# Driver4BusV1_1.net
KiCad netlist of a schematic drawn in Altium Designer
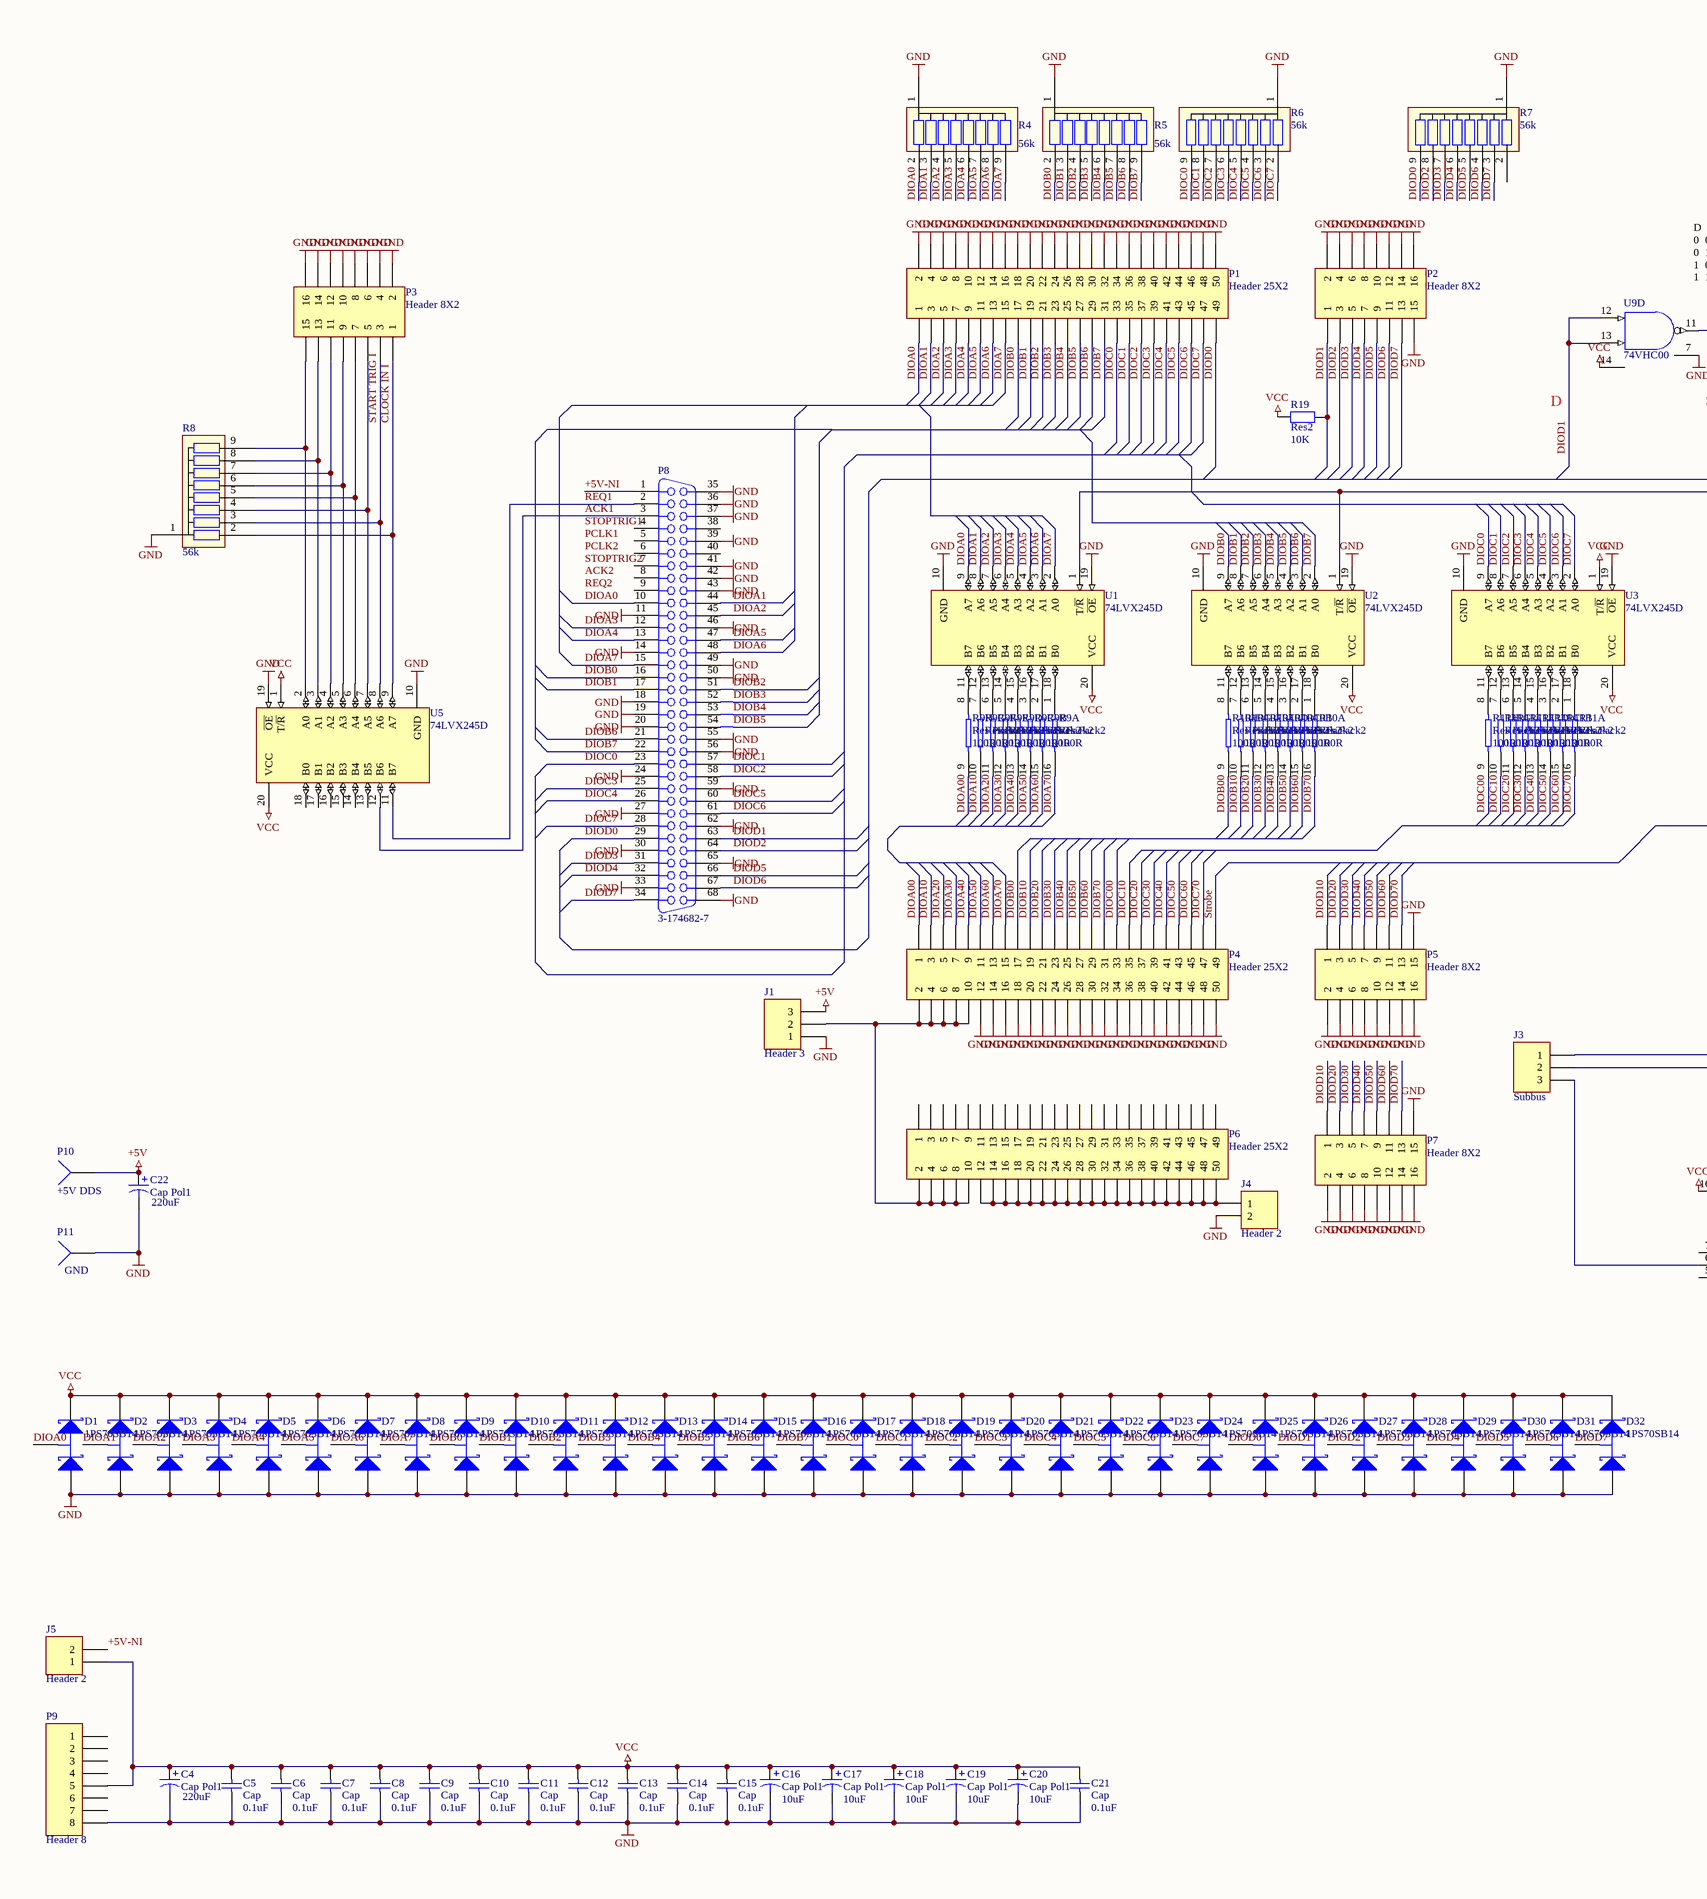
[diagram p0: Driver4BusV1.1.SchDoc, left]
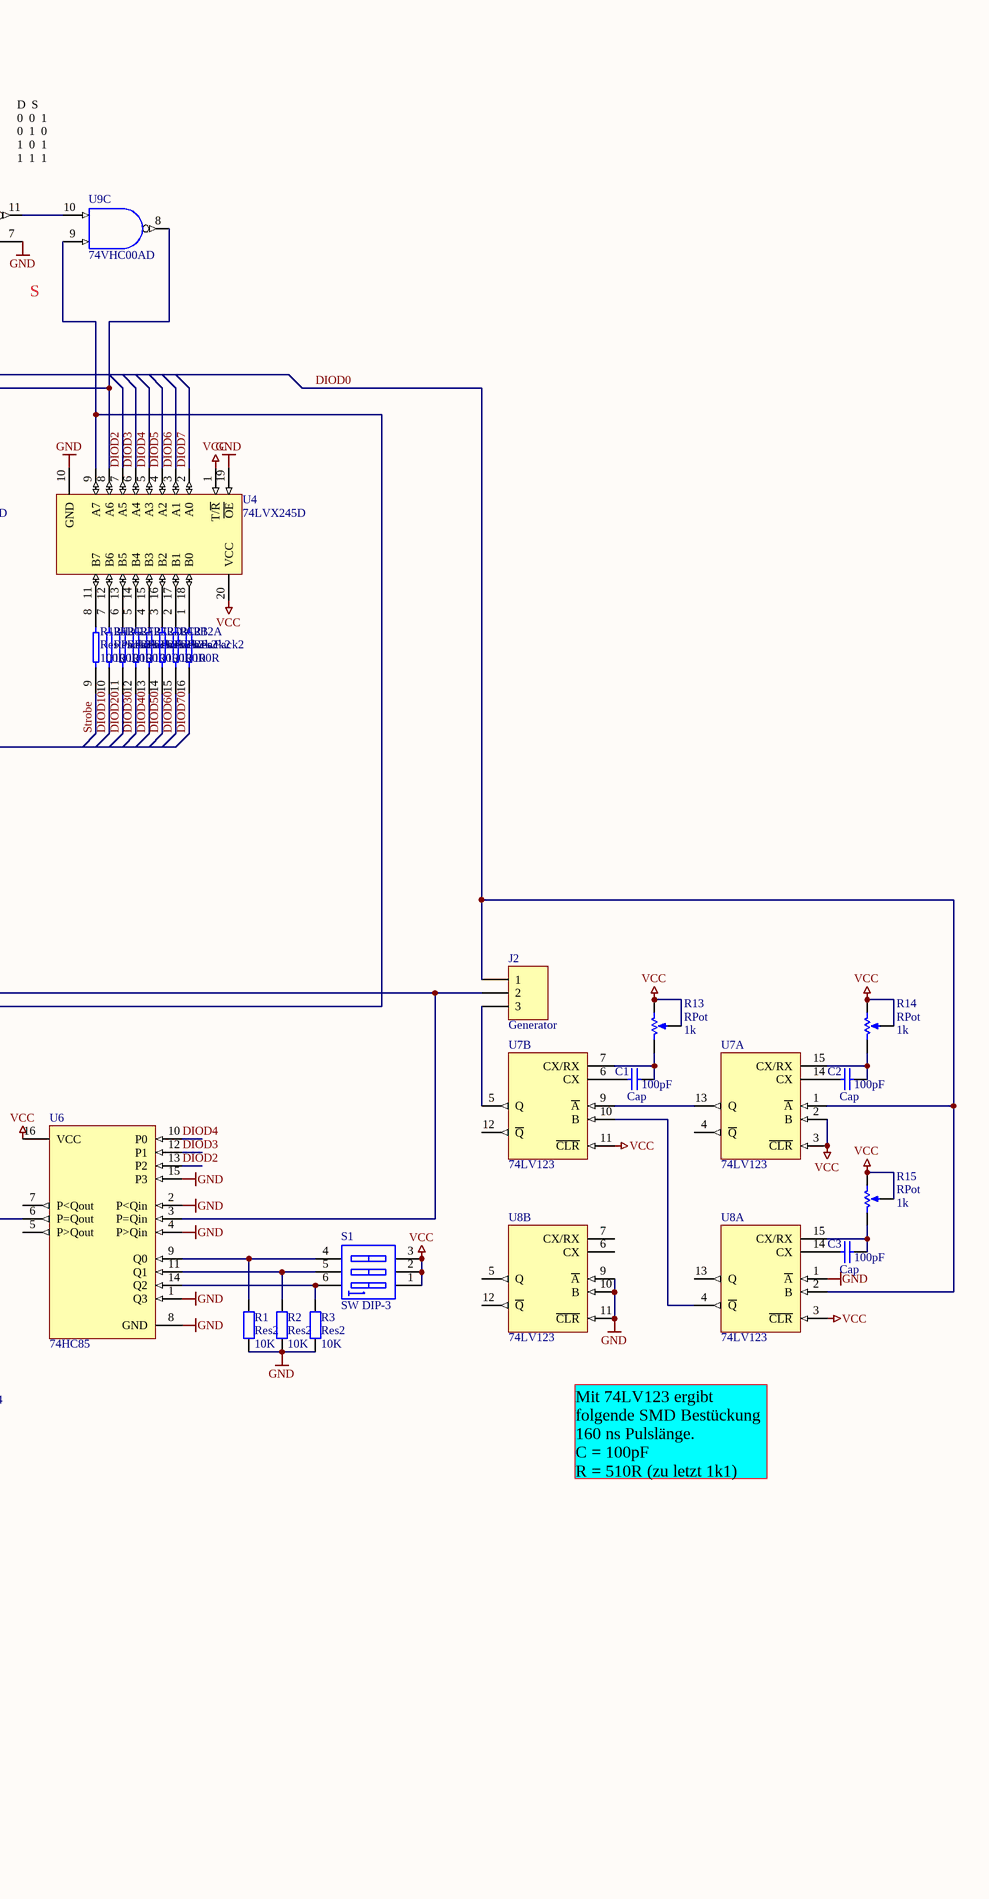
[diagram p1: Driver4BusV1.1.SchDoc, right]

(export (version "E")
  (design (tool "Eeschema 10.0.6"))
  (components
    (comp (ref "C1")
      (value "Cap")
      (footprint "CAPC3216M")
      (description "Capacitor")
      (fields (field (name "ALTIUM_VALUE") "100pF") (field (name "PUBLISHER") "Altium Limited"))
      (libsource (lib "Miscellaneous Devices") (part "Cap"))
    )
    (comp (ref "C2")
      (value "Cap")
      (footprint "CAPC3216M")
      (description "Capacitor")
      (fields (field (name "ALTIUM_VALUE") "100pF") (field (name "PUBLISHER") "Altium Limited"))
      (libsource (lib "Miscellaneous Devices") (part "Cap"))
    )
    (comp (ref "C3")
      (value "Cap")
      (footprint "CAPC3216M")
      (description "Capacitor")
      (fields (field (name "ALTIUM_VALUE") "100pF") (field (name "PUBLISHER") "Altium Limited"))
      (libsource (lib "Miscellaneous Devices") (part "Cap"))
    )
    (comp (ref "C4")
      (value "Cap Pol1")
      (footprint "ElkoSMD8")
      (description "Polarized Capacitor (Radial)")
      (fields (field (name "ALTIUM_VALUE") "220uF") (field (name "PUBLISHER") "Altium Limited"))
      (libsource (lib "Miscellaneous Devices") (part "Cap Pol1"))
    )
    (comp (ref "C5")
      (value "Cap")
      (footprint "CAPC3216M")
      (description "Capacitor")
      (fields (field (name "ALTIUM_VALUE") "0.1uF") (field (name "PUBLISHER") "Altium Limited"))
      (libsource (lib "Miscellaneous Devices") (part "Cap"))
    )
    (comp (ref "C6")
      (value "Cap")
      (footprint "CAPC3216M")
      (description "Capacitor")
      (fields (field (name "ALTIUM_VALUE") "0.1uF") (field (name "PUBLISHER") "Altium Limited"))
      (libsource (lib "Miscellaneous Devices") (part "Cap"))
    )
    (comp (ref "C7")
      (value "Cap")
      (footprint "CAPC3216M")
      (description "Capacitor")
      (fields (field (name "ALTIUM_VALUE") "0.1uF") (field (name "PUBLISHER") "Altium Limited"))
      (libsource (lib "Miscellaneous Devices") (part "Cap"))
    )
    (comp (ref "C8")
      (value "Cap")
      (footprint "CAPC3216M")
      (description "Capacitor")
      (fields (field (name "ALTIUM_VALUE") "0.1uF") (field (name "PUBLISHER") "Altium Limited"))
      (libsource (lib "Miscellaneous Devices") (part "Cap"))
    )
    (comp (ref "C9")
      (value "Cap")
      (footprint "CAPC3216M")
      (description "Capacitor")
      (fields (field (name "ALTIUM_VALUE") "0.1uF") (field (name "PUBLISHER") "Altium Limited"))
      (libsource (lib "Miscellaneous Devices") (part "Cap"))
    )
    (comp (ref "C10")
      (value "Cap")
      (footprint "CAPC3216M")
      (description "Capacitor")
      (fields (field (name "ALTIUM_VALUE") "0.1uF") (field (name "PUBLISHER") "Altium Limited"))
      (libsource (lib "Miscellaneous Devices") (part "Cap"))
    )
    (comp (ref "C11")
      (value "Cap")
      (footprint "CAPC3216M")
      (description "Capacitor")
      (fields (field (name "ALTIUM_VALUE") "0.1uF") (field (name "PUBLISHER") "Altium Limited"))
      (libsource (lib "Miscellaneous Devices") (part "Cap"))
    )
    (comp (ref "C12")
      (value "Cap")
      (footprint "CAPC3216M")
      (description "Capacitor")
      (fields (field (name "ALTIUM_VALUE") "0.1uF") (field (name "PUBLISHER") "Altium Limited"))
      (libsource (lib "Miscellaneous Devices") (part "Cap"))
    )
    (comp (ref "C13")
      (value "Cap")
      (footprint "CAPC3216M")
      (description "Capacitor")
      (fields (field (name "ALTIUM_VALUE") "0.1uF") (field (name "PUBLISHER") "Altium Limited"))
      (libsource (lib "Miscellaneous Devices") (part "Cap"))
    )
    (comp (ref "C14")
      (value "Cap")
      (footprint "CAPC3216M")
      (description "Capacitor")
      (fields (field (name "ALTIUM_VALUE") "0.1uF") (field (name "PUBLISHER") "Altium Limited"))
      (libsource (lib "Miscellaneous Devices") (part "Cap"))
    )
    (comp (ref "C15")
      (value "Cap")
      (footprint "CAPC3216M")
      (description "Capacitor")
      (fields (field (name "ALTIUM_VALUE") "0.1uF") (field (name "PUBLISHER") "Altium Limited"))
      (libsource (lib "Miscellaneous Devices") (part "Cap"))
    )
    (comp (ref "C16")
      (value "Cap Pol1")
      (footprint "TC3528-1411")
      (description "Polarized Capacitor (Radial)")
      (fields (field (name "ALTIUM_VALUE") "10uF") (field (name "PUBLISHER") "Altium Limited"))
      (libsource (lib "Miscellaneous Devices") (part "Cap Pol1"))
    )
    (comp (ref "C17")
      (value "Cap Pol1")
      (footprint "TC3528-1411")
      (description "Polarized Capacitor (Radial)")
      (fields (field (name "ALTIUM_VALUE") "10uF") (field (name "PUBLISHER") "Altium Limited"))
      (libsource (lib "Miscellaneous Devices") (part "Cap Pol1"))
    )
    (comp (ref "C18")
      (value "Cap Pol1")
      (footprint "TC3528-1411")
      (description "Polarized Capacitor (Radial)")
      (fields (field (name "ALTIUM_VALUE") "10uF") (field (name "PUBLISHER") "Altium Limited"))
      (libsource (lib "Miscellaneous Devices") (part "Cap Pol1"))
    )
    (comp (ref "C19")
      (value "Cap Pol1")
      (footprint "TC3528-1411")
      (description "Polarized Capacitor (Radial)")
      (fields (field (name "ALTIUM_VALUE") "10uF") (field (name "PUBLISHER") "Altium Limited"))
      (libsource (lib "Miscellaneous Devices") (part "Cap Pol1"))
    )
    (comp (ref "C20")
      (value "Cap Pol1")
      (footprint "TC3528-1411")
      (description "Polarized Capacitor (Radial)")
      (fields (field (name "ALTIUM_VALUE") "10uF") (field (name "PUBLISHER") "Altium Limited"))
      (libsource (lib "Miscellaneous Devices") (part "Cap Pol1"))
    )
    (comp (ref "C21")
      (value "Cap")
      (footprint "CAPC3216M")
      (description "Capacitor")
      (fields (field (name "ALTIUM_VALUE") "0.1uF") (field (name "PUBLISHER") "Altium Limited"))
      (libsource (lib "Miscellaneous Devices") (part "Cap"))
    )
    (comp (ref "C22")
      (value "Cap Pol1")
      (footprint "ElkoSMD8")
      (description "Polarized Capacitor (Radial)")
      (fields
        (field (name "ALTIUM_VALUE") "220uF")
        (field (name "VOLTAGE") "25V")
        (field (name "PUBLISHER") "Altium Limited")
      )
      (libsource (lib "Miscellaneous Devices") (part "Cap Pol1"))
    )
    (comp (ref "D1")
      (value "1PS70SB14")
      (footprint "SOT323")
      (description "Schottky Barrier Double Diode")
      (fields (field (name "PUBLISHER") "Altium Limited"))
      (libsource (lib "Philips Discrete Diode - Schottky") (part "1PS70SB14"))
    )
    (comp (ref "D2")
      (value "1PS70SB14")
      (footprint "SOT323")
      (description "Schottky Barrier Double Diode")
      (fields (field (name "PUBLISHER") "Altium Limited"))
      (libsource (lib "Philips Discrete Diode - Schottky") (part "1PS70SB14"))
    )
    (comp (ref "D3")
      (value "1PS70SB14")
      (footprint "SOT323")
      (description "Schottky Barrier Double Diode")
      (fields (field (name "PUBLISHER") "Altium Limited"))
      (libsource (lib "Philips Discrete Diode - Schottky") (part "1PS70SB14"))
    )
    (comp (ref "D4")
      (value "1PS70SB14")
      (footprint "SOT323")
      (description "Schottky Barrier Double Diode")
      (fields (field (name "PUBLISHER") "Altium Limited"))
      (libsource (lib "Philips Discrete Diode - Schottky") (part "1PS70SB14"))
    )
    (comp (ref "D5")
      (value "1PS70SB14")
      (footprint "SOT323")
      (description "Schottky Barrier Double Diode")
      (fields (field (name "PUBLISHER") "Altium Limited"))
      (libsource (lib "Philips Discrete Diode - Schottky") (part "1PS70SB14"))
    )
    (comp (ref "D6")
      (value "1PS70SB14")
      (footprint "SOT323")
      (description "Schottky Barrier Double Diode")
      (fields (field (name "PUBLISHER") "Altium Limited"))
      (libsource (lib "Philips Discrete Diode - Schottky") (part "1PS70SB14"))
    )
    (comp (ref "D7")
      (value "1PS70SB14")
      (footprint "SOT323")
      (description "Schottky Barrier Double Diode")
      (fields (field (name "PUBLISHER") "Altium Limited"))
      (libsource (lib "Philips Discrete Diode - Schottky") (part "1PS70SB14"))
    )
    (comp (ref "D8")
      (value "1PS70SB14")
      (footprint "SOT323")
      (description "Schottky Barrier Double Diode")
      (fields (field (name "PUBLISHER") "Altium Limited"))
      (libsource (lib "Philips Discrete Diode - Schottky") (part "1PS70SB14"))
    )
    (comp (ref "D9")
      (value "1PS70SB14")
      (footprint "SOT323")
      (description "Schottky Barrier Double Diode")
      (fields (field (name "PUBLISHER") "Altium Limited"))
      (libsource (lib "Philips Discrete Diode - Schottky") (part "1PS70SB14"))
    )
    (comp (ref "D10")
      (value "1PS70SB14")
      (footprint "SOT323")
      (description "Schottky Barrier Double Diode")
      (fields (field (name "PUBLISHER") "Altium Limited"))
      (libsource (lib "Philips Discrete Diode - Schottky") (part "1PS70SB14"))
    )
    (comp (ref "D11")
      (value "1PS70SB14")
      (footprint "SOT323")
      (description "Schottky Barrier Double Diode")
      (fields (field (name "PUBLISHER") "Altium Limited"))
      (libsource (lib "Philips Discrete Diode - Schottky") (part "1PS70SB14"))
    )
    (comp (ref "D12")
      (value "1PS70SB14")
      (footprint "SOT323")
      (description "Schottky Barrier Double Diode")
      (fields (field (name "PUBLISHER") "Altium Limited"))
      (libsource (lib "Philips Discrete Diode - Schottky") (part "1PS70SB14"))
    )
    (comp (ref "D13")
      (value "1PS70SB14")
      (footprint "SOT323")
      (description "Schottky Barrier Double Diode")
      (fields (field (name "PUBLISHER") "Altium Limited"))
      (libsource (lib "Philips Discrete Diode - Schottky") (part "1PS70SB14"))
    )
    (comp (ref "D14")
      (value "1PS70SB14")
      (footprint "SOT323")
      (description "Schottky Barrier Double Diode")
      (fields (field (name "PUBLISHER") "Altium Limited"))
      (libsource (lib "Philips Discrete Diode - Schottky") (part "1PS70SB14"))
    )
    (comp (ref "D15")
      (value "1PS70SB14")
      (footprint "SOT323")
      (description "Schottky Barrier Double Diode")
      (fields (field (name "PUBLISHER") "Altium Limited"))
      (libsource (lib "Philips Discrete Diode - Schottky") (part "1PS70SB14"))
    )
    (comp (ref "D16")
      (value "1PS70SB14")
      (footprint "SOT323")
      (description "Schottky Barrier Double Diode")
      (fields (field (name "PUBLISHER") "Altium Limited"))
      (libsource (lib "Philips Discrete Diode - Schottky") (part "1PS70SB14"))
    )
    (comp (ref "D17")
      (value "1PS70SB14")
      (footprint "SOT323")
      (description "Schottky Barrier Double Diode")
      (fields (field (name "PUBLISHER") "Altium Limited"))
      (libsource (lib "Philips Discrete Diode - Schottky") (part "1PS70SB14"))
    )
    (comp (ref "D18")
      (value "1PS70SB14")
      (footprint "SOT323")
      (description "Schottky Barrier Double Diode")
      (fields (field (name "PUBLISHER") "Altium Limited"))
      (libsource (lib "Philips Discrete Diode - Schottky") (part "1PS70SB14"))
    )
    (comp (ref "D19")
      (value "1PS70SB14")
      (footprint "SOT323")
      (description "Schottky Barrier Double Diode")
      (fields (field (name "PUBLISHER") "Altium Limited"))
      (libsource (lib "Philips Discrete Diode - Schottky") (part "1PS70SB14"))
    )
    (comp (ref "D20")
      (value "1PS70SB14")
      (footprint "SOT323")
      (description "Schottky Barrier Double Diode")
      (fields (field (name "PUBLISHER") "Altium Limited"))
      (libsource (lib "Philips Discrete Diode - Schottky") (part "1PS70SB14"))
    )
    (comp (ref "D21")
      (value "1PS70SB14")
      (footprint "SOT323")
      (description "Schottky Barrier Double Diode")
      (fields (field (name "PUBLISHER") "Altium Limited"))
      (libsource (lib "Philips Discrete Diode - Schottky") (part "1PS70SB14"))
    )
    (comp (ref "D22")
      (value "1PS70SB14")
      (footprint "SOT323")
      (description "Schottky Barrier Double Diode")
      (fields (field (name "PUBLISHER") "Altium Limited"))
      (libsource (lib "Philips Discrete Diode - Schottky") (part "1PS70SB14"))
    )
    (comp (ref "D23")
      (value "1PS70SB14")
      (footprint "SOT323")
      (description "Schottky Barrier Double Diode")
      (fields (field (name "PUBLISHER") "Altium Limited"))
      (libsource (lib "Philips Discrete Diode - Schottky") (part "1PS70SB14"))
    )
    (comp (ref "D24")
      (value "1PS70SB14")
      (footprint "SOT323")
      (description "Schottky Barrier Double Diode")
      (fields (field (name "PUBLISHER") "Altium Limited"))
      (libsource (lib "Philips Discrete Diode - Schottky") (part "1PS70SB14"))
    )
    (comp (ref "D25")
      (value "1PS70SB14")
      (footprint "SOT323")
      (description "Schottky Barrier Double Diode")
      (fields (field (name "PUBLISHER") "Altium Limited"))
      (libsource (lib "Philips Discrete Diode - Schottky") (part "1PS70SB14"))
    )
    (comp (ref "D26")
      (value "1PS70SB14")
      (footprint "SOT323")
      (description "Schottky Barrier Double Diode")
      (fields (field (name "PUBLISHER") "Altium Limited"))
      (libsource (lib "Philips Discrete Diode - Schottky") (part "1PS70SB14"))
    )
    (comp (ref "D27")
      (value "1PS70SB14")
      (footprint "SOT323")
      (description "Schottky Barrier Double Diode")
      (fields (field (name "PUBLISHER") "Altium Limited"))
      (libsource (lib "Philips Discrete Diode - Schottky") (part "1PS70SB14"))
    )
    (comp (ref "D28")
      (value "1PS70SB14")
      (footprint "SOT323")
      (description "Schottky Barrier Double Diode")
      (fields (field (name "PUBLISHER") "Altium Limited"))
      (libsource (lib "Philips Discrete Diode - Schottky") (part "1PS70SB14"))
    )
    (comp (ref "D29")
      (value "1PS70SB14")
      (footprint "SOT323")
      (description "Schottky Barrier Double Diode")
      (fields (field (name "PUBLISHER") "Altium Limited"))
      (libsource (lib "Philips Discrete Diode - Schottky") (part "1PS70SB14"))
    )
    (comp (ref "D30")
      (value "1PS70SB14")
      (footprint "SOT323")
      (description "Schottky Barrier Double Diode")
      (fields (field (name "PUBLISHER") "Altium Limited"))
      (libsource (lib "Philips Discrete Diode - Schottky") (part "1PS70SB14"))
    )
    (comp (ref "D31")
      (value "1PS70SB14")
      (footprint "SOT323")
      (description "Schottky Barrier Double Diode")
      (fields (field (name "PUBLISHER") "Altium Limited"))
      (libsource (lib "Philips Discrete Diode - Schottky") (part "1PS70SB14"))
    )
    (comp (ref "D32")
      (value "1PS70SB14")
      (footprint "SOT323")
      (description "Schottky Barrier Double Diode")
      (fields (field (name "PUBLISHER") "Altium Limited"))
      (libsource (lib "Philips Discrete Diode - Schottky") (part "1PS70SB14"))
    )
    (comp (ref "J1")
      (value "Header 3")
      (footprint "HDR1X3")
      (description "Header, 3-Pin")
      (fields (field (name "PUBLISHER") "Altium Limited"))
      (libsource (lib "") (part "Header 3_2"))
    )
    (comp (ref "J2")
      (value "Generator")
      (footprint "HDR1X3")
      (description "Header, 3-Pin")
      (fields (field (name "PUBLISHER") "Altium Limited"))
      (libsource (lib "") (part "Header 3_1"))
    )
    (comp (ref "J3")
      (value "Subbus")
      (footprint "HDR1X3")
      (description "Header, 3-Pin")
      (fields (field (name "PUBLISHER") "Altium Limited"))
      (libsource (lib "Miscellaneous Connectors") (part "Header 3"))
    )
    (comp (ref "J4")
      (value "Header 2")
      (footprint "RESC2012M")
      (description "Header, 2-Pin")
      (fields (field (name "PUBLISHER") "Altium Limited"))
      (libsource (lib "Miscellaneous Connectors") (part "Header 2"))
    )
    (comp (ref "J5")
      (value "Header 2")
      (footprint "RESC2012M")
      (description "Header, 2-Pin")
      (fields (field (name "PUBLISHER") "Altium Limited"))
      (libsource (lib "") (part "Header 2_1"))
    )
    (comp (ref "P1")
      (value "Header 25X2")
      (footprint "HDR2X25")
      (description "Header, 25-Pin, Dual row")
      (fields (field (name "PUBLISHER") "Altium Limited"))
      (libsource (lib "") (part "Header 25X2_1"))
    )
    (comp (ref "P2")
      (value "Header 8X2")
      (footprint "HDR2X8")
      (description "Header, 8-Pin, Dual row")
      (fields (field (name "PUBLISHER") "Altium Limited"))
      (libsource (lib "") (part "Header 8X2_2"))
    )
    (comp (ref "P3")
      (value "Header 8X2")
      (footprint "HDR2X8")
      (description "Header, 8-Pin, Dual row")
      (fields (field (name "PUBLISHER") "Altium Limited"))
      (libsource (lib "Miscellaneous Connectors") (part "Header 8X2"))
    )
    (comp (ref "P4")
      (value "Header 25X2")
      (footprint "HDR2X25")
      (description "Header, 25-Pin, Dual row")
      (fields (field (name "PUBLISHER") "Altium Limited"))
      (libsource (lib "Miscellaneous Connectors") (part "Header 25X2"))
    )
    (comp (ref "P5")
      (value "Header 8X2")
      (footprint "HDR2X8")
      (description "Header, 8-Pin, Dual row")
      (fields (field (name "PUBLISHER") "Altium Limited"))
      (libsource (lib "") (part "Header 8X2_1"))
    )
    (comp (ref "P6")
      (value "Header 25X2")
      (footprint "HDR2X25")
      (description "Header, 25-Pin, Dual row")
      (fields (field (name "PUBLISHER") "Altium Limited"))
      (libsource (lib "Miscellaneous Connectors") (part "Header 25X2"))
    )
    (comp (ref "P7")
      (value "Header 8X2")
      (footprint "HDR2X8")
      (description "Header, 8-Pin, Dual row")
      (fields (field (name "PUBLISHER") "Altium Limited"))
      (libsource (lib "") (part "Header 8X2_1"))
    )
    (comp (ref "P8")
      (value "3-174682-7")
      (footprint "174225-5")
      (description "Plug Assembly, Horizontal with Kink")
      (fields (field (name "PUBLISHER") "Altium Limited"))
      (libsource (lib "AMP D Subminiature 050 Series") (part "3-174682-7"))
    )
    (comp (ref "P9")
      (value "Header 8")
      (footprint "DIN 8-polig V2")
      (description "Header, 8-Pin")
      (fields (field (name "PUBLISHER") "Altium Limited"))
      (libsource (lib "Miscellaneous Connectors") (part "Header 8"))
    )
    (comp (ref "P10")
      (value "+5V DDS")
      (footprint "Banane on BCP")
      (description "Socket")
      (fields (field (name "PUBLISHER") "Altium Limited"))
      (libsource (lib "Miscellaneous Connectors") (part "Socket"))
    )
    (comp (ref "P11")
      (value "GND")
      (footprint "Banane on BCP")
      (description "Socket")
      (fields (field (name "PUBLISHER") "Altium Limited"))
      (libsource (lib "Miscellaneous Connectors") (part "Socket"))
    )
    (comp (ref "R1")
      (value "Res2")
      (footprint "3216[1206]")
      (description "Resistor")
      (fields (field (name "ALTIUM_VALUE") "10K") (field (name "PUBLISHER") "Altium Limited"))
      (libsource (lib "Miscellaneous Devices") (part "Res2"))
    )
    (comp (ref "R2")
      (value "Res2")
      (footprint "3216[1206]")
      (description "Resistor")
      (fields (field (name "ALTIUM_VALUE") "10K") (field (name "PUBLISHER") "Altium Limited"))
      (libsource (lib "Miscellaneous Devices") (part "Res2"))
    )
    (comp (ref "R3")
      (value "Res2")
      (footprint "3216[1206]")
      (description "Resistor")
      (fields (field (name "ALTIUM_VALUE") "10K") (field (name "PUBLISHER") "Altium Limited"))
      (libsource (lib "Miscellaneous Devices") (part "Res2"))
    )
    (comp (ref "R4")
      (value "56k")
      (footprint "Widerstandnetzwerk 4609X")
      (fields (field (name "Comment") "Widerstandnetzwerk 4609X"))
      (libsource (lib "") (part "Widerstandnetzwerk 4609X_1"))
    )
    (comp (ref "R5")
      (value "56k")
      (footprint "Widerstandnetzwerk 4609X")
      (fields (field (name "Comment") "Widerstandnetzwerk 4609X"))
      (libsource (lib "") (part "Widerstandnetzwerk 4609X_1"))
    )
    (comp (ref "R6")
      (value "56k")
      (footprint "Widerstandnetzwerk 4609X")
      (fields (field (name "Comment") "Widerstandnetzwerk 4609X"))
      (libsource (lib "eigene") (part "Widerstandnetzwerk 4609X"))
    )
    (comp (ref "R7")
      (value "56k")
      (footprint "Widerstandnetzwerk 4609X")
      (fields (field (name "Comment") "Widerstandnetzwerk 4609X"))
      (libsource (lib "eigene") (part "Widerstandnetzwerk 4609X"))
    )
    (comp (ref "R8")
      (value "56k")
      (footprint "Widerstandnetzwerk 4609X")
      (fields (field (name "Comment") "Widerstandnetzwerk 4609X"))
      (libsource (lib "") (part "Widerstandnetzwerk 4609X_2"))
    )
    (comp (ref "R9")
      (value "Res Pack2")
      (footprint "SOIC-OE16_M")
      (description "Isolated Resistor Network - Parts")
      (fields (field (name "ALTIUM_VALUE") "100R") (field (name "PUBLISHER") "Altium Limited"))
      (libsource (lib "Miscellaneous Devices") (part "Res Pack2"))
    )
    (comp (ref "R10")
      (value "Res Pack2")
      (footprint "SOIC-OE16_M")
      (description "Isolated Resistor Network - Parts")
      (fields (field (name "ALTIUM_VALUE") "100R") (field (name "PUBLISHER") "Altium Limited"))
      (libsource (lib "Miscellaneous Devices") (part "Res Pack2"))
    )
    (comp (ref "R11")
      (value "Res Pack2")
      (footprint "SOIC-OE16_M")
      (description "Isolated Resistor Network - Parts")
      (fields (field (name "ALTIUM_VALUE") "100R") (field (name "PUBLISHER") "Altium Limited"))
      (libsource (lib "Miscellaneous Devices") (part "Res Pack2"))
    )
    (comp (ref "R12")
      (value "Res Pack2")
      (footprint "SOIC-OE16_M")
      (description "Isolated Resistor Network - Parts")
      (fields (field (name "ALTIUM_VALUE") "100R") (field (name "PUBLISHER") "Altium Limited"))
      (libsource (lib "Miscellaneous Devices") (part "Res Pack2"))
    )
    (comp (ref "R13")
      (value "RPot")
      (footprint "rpot3")
      (description "Potentiometer")
      (fields (field (name "ALTIUM_VALUE") "1k") (field (name "PUBLISHER") "Altium Limited"))
      (libsource (lib "Miscellaneous Devices") (part "RPot"))
    )
    (comp (ref "R14")
      (value "RPot")
      (footprint "rpot3")
      (description "Potentiometer")
      (fields (field (name "ALTIUM_VALUE") "1k") (field (name "PUBLISHER") "Altium Limited"))
      (libsource (lib "Miscellaneous Devices") (part "RPot"))
    )
    (comp (ref "R15")
      (value "RPot")
      (footprint "rpot3")
      (description "Potentiometer")
      (fields (field (name "ALTIUM_VALUE") "1k") (field (name "PUBLISHER") "Altium Limited"))
      (libsource (lib "Miscellaneous Devices") (part "RPot"))
    )
    (comp (ref "R19")
      (value "Res2")
      (footprint "3216[1206]")
      (description "Resistor")
      (fields (field (name "ALTIUM_VALUE") "10K") (field (name "PUBLISHER") "Altium Limited"))
      (libsource (lib "") (part "Res2_1"))
    )
    (comp (ref "S1")
      (value "SW DIP-3")
      (footprint "DIP-6")
      (description "DIP Switch, 3 Position, SPST")
      (fields (field (name "PUBLISHER") "Altium Limited"))
      (libsource (lib "Miscellaneous Devices") (part "SW DIP-3"))
    )
    (comp (ref "U1")
      (value "74LVX245D")
      (footprint "DW020_N")
      (description "Octal Bus Transceiver with 3-State Outputs")
      (fields (field (name "PUBLISHER") "Altium Limited"))
      (libsource (lib "TI Interface 8-Bit Line Transceiver") (part "SN74HC245DW"))
    )
    (comp (ref "U2")
      (value "74LVX245D")
      (footprint "DW020_N")
      (description "Octal Bus Transceiver with 3-State Outputs")
      (fields (field (name "PUBLISHER") "Altium Limited"))
      (libsource (lib "TI Interface 8-Bit Line Transceiver") (part "SN74HC245DW"))
    )
    (comp (ref "U3")
      (value "74LVX245D")
      (footprint "DW020_N")
      (description "Octal Bus Transceiver with 3-State Outputs")
      (fields (field (name "PUBLISHER") "Altium Limited"))
      (libsource (lib "TI Interface 8-Bit Line Transceiver") (part "SN74HC245DW"))
    )
    (comp (ref "U4")
      (value "74LVX245D")
      (footprint "DW020_N")
      (description "Octal Bus Transceiver with 3-State Outputs")
      (fields (field (name "PUBLISHER") "Altium Limited"))
      (libsource (lib "TI Interface 8-Bit Line Transceiver") (part "SN74HC245DW"))
    )
    (comp (ref "U5")
      (value "74LVX245D")
      (footprint "DW020_N")
      (description "Octal Bus Transceiver with 3-State Outputs")
      (fields (field (name "PUBLISHER") "Altium Limited"))
      (libsource (lib "") (part "SN74HC245DW_1"))
    )
    (comp (ref "U6")
      (value "74HC85")
      (footprint "SO16_M")
      (description "4-Bit Magnitude Comparator")
      (fields (field (name "PUBLISHER") "Altium Limited"))
      (libsource (lib "ST Logic Comparator") (part "M74HC85M1R"))
    )
    (comp (ref "U7")
      (value "74LV123")
      (footprint "SO16_N")
      (description "Dual Retriggerable Monostable Multivibrator")
      (fields (field (name "PUBLISHER") "Altium Limited"))
      (libsource (lib "ST Logic Multivibrator") (part "M74HC123AM1R"))
    )
    (comp (ref "U8")
      (value "74LV123")
      (footprint "SO16_N")
      (description "Dual Retriggerable Monostable Multivibrator")
      (fields (field (name "PUBLISHER") "Altium Limited"))
      (libsource (lib "ST Logic Multivibrator") (part "M74HC123AM1R"))
    )
    (comp (ref "U9")
      (value "74VHC00AD")
      (footprint "751A-02_N")
      (description "Quad 2-Input NAND Gate")
      (fields (field (name "PUBLISHER") "Altium Limited"))
      (libsource (lib "") (part "MC74HC00AD_1"))
    )
  )
  (nets
    (net (code "1") (name "+5V") (class "Default")
      (node (ref "C22") (pin "1") (pinfunction "1_1") (pintype "passive"))
      (node (ref "J1") (pin "3") (pinfunction "3_3") (pintype "passive"))
      (node (ref "P10") (pin "1") (pinfunction "1_1") (pintype "passive"))
    )
    (net (code "2") (name "/+5V-NI") (class "Default")
      (node (ref "J5") (pin "2") (pinfunction "2_2") (pintype "passive"))
      (node (ref "P8") (pin "1") (pinfunction "1_1") (pintype "passive"))
    )
    (net (code "3") (name "/ACK1") (class "Default")
      (node (ref "P8") (pin "3") (pinfunction "3_3") (pintype "passive"))
      (node (ref "U5") (pin "12") (pinfunction "B6_12") (pintype "bidirectional"))
    )
    (net (code "5") (name "/CLOCK IN I") (class "Default")
      (node (ref "P3") (pin "1") (pinfunction "1_1") (pintype "passive"))
      (node (ref "R8") (pin "2") (pinfunction "2_2") (pintype "passive"))
      (node (ref "U5") (pin "9") (pinfunction "A7_9") (pintype "bidirectional"))
    )
    (net (code "6") (name "/DIOA00") (class "Default")
      (node (ref "P4") (pin "1") (pinfunction "1_1") (pintype "passive"))
      (node (ref "R9") (pin "9") (pinfunction "9_9") (pintype "passive"))
    )
    (net (code "7") (name "/DIOA0") (class "Default")
      (node (ref "D1") (pin "3") (pinfunction "C_3") (pintype "passive"))
      (node (ref "P1") (pin "1") (pinfunction "1_1") (pintype "passive"))
      (node (ref "P8") (pin "10") (pinfunction "10_10") (pintype "passive"))
      (node (ref "R4") (pin "2") (pinfunction "2_2") (pintype "passive"))
      (node (ref "U1") (pin "9") (pinfunction "A7_9") (pintype "bidirectional"))
    )
    (net (code "8") (name "/DIOA1") (class "Default")
      (node (ref "D2") (pin "3") (pinfunction "C_3") (pintype "passive"))
      (node (ref "P1") (pin "3") (pinfunction "3_3") (pintype "passive"))
      (node (ref "P8") (pin "44") (pinfunction "44_44") (pintype "passive"))
      (node (ref "R4") (pin "3") (pinfunction "3_3") (pintype "passive"))
      (node (ref "U1") (pin "8") (pinfunction "A6_8") (pintype "bidirectional"))
    )
    (net (code "9") (name "/DIOA2") (class "Default")
      (node (ref "D3") (pin "3") (pinfunction "C_3") (pintype "passive"))
      (node (ref "P1") (pin "5") (pinfunction "5_5") (pintype "passive"))
      (node (ref "P8") (pin "45") (pinfunction "45_45") (pintype "passive"))
      (node (ref "R4") (pin "4") (pinfunction "4_4") (pintype "passive"))
      (node (ref "U1") (pin "7") (pinfunction "A5_7") (pintype "bidirectional"))
    )
    (net (code "10") (name "/DIOA3") (class "Default")
      (node (ref "D4") (pin "3") (pinfunction "C_3") (pintype "passive"))
      (node (ref "P1") (pin "7") (pinfunction "7_7") (pintype "passive"))
      (node (ref "P8") (pin "12") (pinfunction "12_12") (pintype "passive"))
      (node (ref "R4") (pin "5") (pinfunction "5_5") (pintype "passive"))
      (node (ref "U1") (pin "6") (pinfunction "A4_6") (pintype "bidirectional"))
    )
    (net (code "11") (name "/DIOA4") (class "Default")
      (node (ref "D5") (pin "3") (pinfunction "C_3") (pintype "passive"))
      (node (ref "P1") (pin "9") (pinfunction "9_9") (pintype "passive"))
      (node (ref "P8") (pin "13") (pinfunction "13_13") (pintype "passive"))
      (node (ref "R4") (pin "6") (pinfunction "6_6") (pintype "passive"))
      (node (ref "U1") (pin "5") (pinfunction "A3_5") (pintype "bidirectional"))
    )
    (net (code "12") (name "/DIOA5") (class "Default")
      (node (ref "D6") (pin "3") (pinfunction "C_3") (pintype "passive"))
      (node (ref "P1") (pin "11") (pinfunction "11_11") (pintype "passive"))
      (node (ref "P8") (pin "47") (pinfunction "47_47") (pintype "passive"))
      (node (ref "R4") (pin "7") (pinfunction "7_7") (pintype "passive"))
      (node (ref "U1") (pin "4") (pinfunction "A2_4") (pintype "bidirectional"))
    )
    (net (code "13") (name "/DIOA6") (class "Default")
      (node (ref "D7") (pin "3") (pinfunction "C_3") (pintype "passive"))
      (node (ref "P1") (pin "13") (pinfunction "13_13") (pintype "passive"))
      (node (ref "P8") (pin "48") (pinfunction "48_48") (pintype "passive"))
      (node (ref "R4") (pin "8") (pinfunction "8_8") (pintype "passive"))
      (node (ref "U1") (pin "3") (pinfunction "A1_3") (pintype "bidirectional"))
    )
    (net (code "14") (name "/DIOA7") (class "Default")
      (node (ref "D8") (pin "3") (pinfunction "C_3") (pintype "passive"))
      (node (ref "P1") (pin "15") (pinfunction "15_15") (pintype "passive"))
      (node (ref "P8") (pin "15") (pinfunction "15_15") (pintype "passive"))
      (node (ref "R4") (pin "9") (pinfunction "9_9") (pintype "passive"))
      (node (ref "U1") (pin "2") (pinfunction "A0_2") (pintype "bidirectional"))
    )
    (net (code "15") (name "/DIOA10") (class "Default")
      (node (ref "P4") (pin "3") (pinfunction "3_3") (pintype "passive"))
      (node (ref "R9") (pin "10") (pinfunction "10_10") (pintype "passive"))
    )
    (net (code "16") (name "/DIOA20") (class "Default")
      (node (ref "P4") (pin "5") (pinfunction "5_5") (pintype "passive"))
      (node (ref "R9") (pin "11") (pinfunction "11_11") (pintype "passive"))
    )
    (net (code "17") (name "/DIOA30") (class "Default")
      (node (ref "P4") (pin "7") (pinfunction "7_7") (pintype "passive"))
      (node (ref "R9") (pin "12") (pinfunction "12_12") (pintype "passive"))
    )
    (net (code "18") (name "/DIOA40") (class "Default")
      (node (ref "P4") (pin "9") (pinfunction "9_9") (pintype "passive"))
      (node (ref "R9") (pin "13") (pinfunction "13_13") (pintype "passive"))
    )
    (net (code "19") (name "/DIOA50") (class "Default")
      (node (ref "P4") (pin "11") (pinfunction "11_11") (pintype "passive"))
      (node (ref "R9") (pin "14") (pinfunction "14_14") (pintype "passive"))
    )
    (net (code "20") (name "/DIOA60") (class "Default")
      (node (ref "P4") (pin "13") (pinfunction "13_13") (pintype "passive"))
      (node (ref "R9") (pin "15") (pinfunction "15_15") (pintype "passive"))
    )
    (net (code "21") (name "/DIOA70") (class "Default")
      (node (ref "P4") (pin "15") (pinfunction "15_15") (pintype "passive"))
      (node (ref "R9") (pin "16") (pinfunction "16_16") (pintype "passive"))
    )
    (net (code "22") (name "/DIOB0") (class "Default")
      (node (ref "D9") (pin "3") (pinfunction "C_3") (pintype "passive"))
      (node (ref "P1") (pin "17") (pinfunction "17_17") (pintype "passive"))
      (node (ref "P8") (pin "16") (pinfunction "16_16") (pintype "passive"))
      (node (ref "R5") (pin "2") (pinfunction "2_2") (pintype "passive"))
      (node (ref "U2") (pin "9") (pinfunction "A7_9") (pintype "bidirectional"))
    )
    (net (code "23") (name "/DIOB00") (class "Default")
      (node (ref "P4") (pin "17") (pinfunction "17_17") (pintype "passive"))
      (node (ref "R10") (pin "9") (pinfunction "9_9") (pintype "passive"))
    )
    (net (code "24") (name "/DIOB1") (class "Default")
      (node (ref "D10") (pin "3") (pinfunction "C_3") (pintype "passive"))
      (node (ref "P1") (pin "19") (pinfunction "19_19") (pintype "passive"))
      (node (ref "P8") (pin "17") (pinfunction "17_17") (pintype "passive"))
      (node (ref "R5") (pin "3") (pinfunction "3_3") (pintype "passive"))
      (node (ref "U2") (pin "8") (pinfunction "A6_8") (pintype "bidirectional"))
    )
    (net (code "25") (name "/DIOB2") (class "Default")
      (node (ref "D11") (pin "3") (pinfunction "C_3") (pintype "passive"))
      (node (ref "P1") (pin "21") (pinfunction "21_21") (pintype "passive"))
      (node (ref "P8") (pin "51") (pinfunction "51_51") (pintype "passive"))
      (node (ref "R5") (pin "4") (pinfunction "4_4") (pintype "passive"))
      (node (ref "U2") (pin "7") (pinfunction "A5_7") (pintype "bidirectional"))
    )
    (net (code "26") (name "/DIOB3") (class "Default")
      (node (ref "D12") (pin "3") (pinfunction "C_3") (pintype "passive"))
      (node (ref "P1") (pin "23") (pinfunction "23_23") (pintype "passive"))
      (node (ref "P8") (pin "52") (pinfunction "52_52") (pintype "passive"))
      (node (ref "R5") (pin "5") (pinfunction "5_5") (pintype "passive"))
      (node (ref "U2") (pin "6") (pinfunction "A4_6") (pintype "bidirectional"))
    )
    (net (code "27") (name "/DIOB4") (class "Default")
      (node (ref "D13") (pin "3") (pinfunction "C_3") (pintype "passive"))
      (node (ref "P1") (pin "25") (pinfunction "25_25") (pintype "passive"))
      (node (ref "P8") (pin "53") (pinfunction "53_53") (pintype "passive"))
      (node (ref "R5") (pin "6") (pinfunction "6_6") (pintype "passive"))
      (node (ref "U2") (pin "5") (pinfunction "A3_5") (pintype "bidirectional"))
    )
    (net (code "28") (name "/DIOB5") (class "Default")
      (node (ref "D14") (pin "3") (pinfunction "C_3") (pintype "passive"))
      (node (ref "P1") (pin "27") (pinfunction "27_27") (pintype "passive"))
      (node (ref "P8") (pin "54") (pinfunction "54_54") (pintype "passive"))
      (node (ref "R5") (pin "7") (pinfunction "7_7") (pintype "passive"))
      (node (ref "U2") (pin "4") (pinfunction "A2_4") (pintype "bidirectional"))
    )
    (net (code "29") (name "/DIOB6") (class "Default")
      (node (ref "D15") (pin "3") (pinfunction "C_3") (pintype "passive"))
      (node (ref "P1") (pin "29") (pinfunction "29_29") (pintype "passive"))
      (node (ref "P8") (pin "21") (pinfunction "21_21") (pintype "passive"))
      (node (ref "R5") (pin "8") (pinfunction "8_8") (pintype "passive"))
      (node (ref "U2") (pin "3") (pinfunction "A1_3") (pintype "bidirectional"))
    )
    (net (code "30") (name "/DIOB7") (class "Default")
      (node (ref "D16") (pin "3") (pinfunction "C_3") (pintype "passive"))
      (node (ref "P1") (pin "31") (pinfunction "31_31") (pintype "passive"))
      (node (ref "P8") (pin "22") (pinfunction "22_22") (pintype "passive"))
      (node (ref "R5") (pin "9") (pinfunction "9_9") (pintype "passive"))
      (node (ref "U2") (pin "2") (pinfunction "A0_2") (pintype "bidirectional"))
    )
    (net (code "31") (name "/DIOB10") (class "Default")
      (node (ref "P4") (pin "19") (pinfunction "19_19") (pintype "passive"))
      (node (ref "R10") (pin "10") (pinfunction "10_10") (pintype "passive"))
    )
    (net (code "32") (name "/DIOB20") (class "Default")
      (node (ref "P4") (pin "21") (pinfunction "21_21") (pintype "passive"))
      (node (ref "R10") (pin "11") (pinfunction "11_11") (pintype "passive"))
    )
    (net (code "33") (name "/DIOB30") (class "Default")
      (node (ref "P4") (pin "23") (pinfunction "23_23") (pintype "passive"))
      (node (ref "R10") (pin "12") (pinfunction "12_12") (pintype "passive"))
    )
    (net (code "34") (name "/DIOB40") (class "Default")
      (node (ref "P4") (pin "25") (pinfunction "25_25") (pintype "passive"))
      (node (ref "R10") (pin "13") (pinfunction "13_13") (pintype "passive"))
    )
    (net (code "35") (name "/DIOB50") (class "Default")
      (node (ref "P4") (pin "27") (pinfunction "27_27") (pintype "passive"))
      (node (ref "R10") (pin "14") (pinfunction "14_14") (pintype "passive"))
    )
    (net (code "36") (name "/DIOB60") (class "Default")
      (node (ref "P4") (pin "29") (pinfunction "29_29") (pintype "passive"))
      (node (ref "R10") (pin "15") (pinfunction "15_15") (pintype "passive"))
    )
    (net (code "37") (name "/DIOB70") (class "Default")
      (node (ref "P4") (pin "31") (pinfunction "31_31") (pintype "passive"))
      (node (ref "R10") (pin "16") (pinfunction "16_16") (pintype "passive"))
    )
    (net (code "38") (name "/DIOC00") (class "Default")
      (node (ref "P4") (pin "33") (pinfunction "33_33") (pintype "passive"))
      (node (ref "R11") (pin "9") (pinfunction "9_9") (pintype "passive"))
    )
    (net (code "39") (name "/DIOC0") (class "Default")
      (node (ref "D17") (pin "3") (pinfunction "C_3") (pintype "passive"))
      (node (ref "P1") (pin "33") (pinfunction "33_33") (pintype "passive"))
      (node (ref "P8") (pin "23") (pinfunction "23_23") (pintype "passive"))
      (node (ref "R6") (pin "9") (pinfunction "9_9") (pintype "passive"))
      (node (ref "U3") (pin "9") (pinfunction "A7_9") (pintype "bidirectional"))
    )
    (net (code "40") (name "/DIOC1") (class "Default")
      (node (ref "D18") (pin "3") (pinfunction "C_3") (pintype "passive"))
      (node (ref "P1") (pin "35") (pinfunction "35_35") (pintype "passive"))
      (node (ref "P8") (pin "57") (pinfunction "57_57") (pintype "passive"))
      (node (ref "R6") (pin "8") (pinfunction "8_8") (pintype "passive"))
      (node (ref "U3") (pin "8") (pinfunction "A6_8") (pintype "bidirectional"))
    )
    (net (code "41") (name "/DIOC2") (class "Default")
      (node (ref "D19") (pin "3") (pinfunction "C_3") (pintype "passive"))
      (node (ref "P1") (pin "37") (pinfunction "37_37") (pintype "passive"))
      (node (ref "P8") (pin "58") (pinfunction "58_58") (pintype "passive"))
      (node (ref "R6") (pin "7") (pinfunction "7_7") (pintype "passive"))
      (node (ref "U3") (pin "7") (pinfunction "A5_7") (pintype "bidirectional"))
    )
    (net (code "42") (name "/DIOC3") (class "Default")
      (node (ref "D20") (pin "3") (pinfunction "C_3") (pintype "passive"))
      (node (ref "P1") (pin "39") (pinfunction "39_39") (pintype "passive"))
      (node (ref "P8") (pin "25") (pinfunction "25_25") (pintype "passive"))
      (node (ref "R6") (pin "6") (pinfunction "6_6") (pintype "passive"))
      (node (ref "U3") (pin "6") (pinfunction "A4_6") (pintype "bidirectional"))
    )
    (net (code "43") (name "/DIOC4") (class "Default")
      (node (ref "D21") (pin "3") (pinfunction "C_3") (pintype "passive"))
      (node (ref "P1") (pin "41") (pinfunction "41_41") (pintype "passive"))
      (node (ref "P8") (pin "26") (pinfunction "26_26") (pintype "passive"))
      (node (ref "R6") (pin "5") (pinfunction "5_5") (pintype "passive"))
      (node (ref "U3") (pin "5") (pinfunction "A3_5") (pintype "bidirectional"))
    )
    (net (code "44") (name "/DIOC5") (class "Default")
      (node (ref "D22") (pin "3") (pinfunction "C_3") (pintype "passive"))
      (node (ref "P1") (pin "43") (pinfunction "43_43") (pintype "passive"))
      (node (ref "P8") (pin "60") (pinfunction "60_60") (pintype "passive"))
      (node (ref "R6") (pin "4") (pinfunction "4_4") (pintype "passive"))
      (node (ref "U3") (pin "4") (pinfunction "A2_4") (pintype "bidirectional"))
    )
    (net (code "45") (name "/DIOC6") (class "Default")
      (node (ref "D23") (pin "3") (pinfunction "C_3") (pintype "passive"))
      (node (ref "P1") (pin "45") (pinfunction "45_45") (pintype "passive"))
      (node (ref "P8") (pin "61") (pinfunction "61_61") (pintype "passive"))
      (node (ref "R6") (pin "3") (pinfunction "3_3") (pintype "passive"))
      (node (ref "U3") (pin "3") (pinfunction "A1_3") (pintype "bidirectional"))
    )
    (net (code "46") (name "/DIOC7") (class "Default")
      (node (ref "D24") (pin "3") (pinfunction "C_3") (pintype "passive"))
      (node (ref "P1") (pin "47") (pinfunction "47_47") (pintype "passive"))
      (node (ref "P8") (pin "28") (pinfunction "28_28") (pintype "passive"))
      (node (ref "R6") (pin "2") (pinfunction "2_2") (pintype "passive"))
      (node (ref "U3") (pin "2") (pinfunction "A0_2") (pintype "bidirectional"))
    )
    (net (code "47") (name "/DIOC10") (class "Default")
      (node (ref "P4") (pin "35") (pinfunction "35_35") (pintype "passive"))
      (node (ref "R11") (pin "10") (pinfunction "10_10") (pintype "passive"))
    )
    (net (code "48") (name "/DIOC20") (class "Default")
      (node (ref "P4") (pin "37") (pinfunction "37_37") (pintype "passive"))
      (node (ref "R11") (pin "11") (pinfunction "11_11") (pintype "passive"))
    )
    (net (code "49") (name "/DIOC30") (class "Default")
      (node (ref "P4") (pin "39") (pinfunction "39_39") (pintype "passive"))
      (node (ref "R11") (pin "12") (pinfunction "12_12") (pintype "passive"))
    )
    (net (code "50") (name "/DIOC40") (class "Default")
      (node (ref "P4") (pin "41") (pinfunction "41_41") (pintype "passive"))
      (node (ref "R11") (pin "13") (pinfunction "13_13") (pintype "passive"))
    )
    (net (code "51") (name "/DIOC50") (class "Default")
      (node (ref "P4") (pin "43") (pinfunction "43_43") (pintype "passive"))
      (node (ref "R11") (pin "14") (pinfunction "14_14") (pintype "passive"))
    )
    (net (code "52") (name "/DIOC60") (class "Default")
      (node (ref "P4") (pin "45") (pinfunction "45_45") (pintype "passive"))
      (node (ref "R11") (pin "15") (pinfunction "15_15") (pintype "passive"))
    )
    (net (code "53") (name "/DIOC70") (class "Default")
      (node (ref "P4") (pin "47") (pinfunction "47_47") (pintype "passive"))
      (node (ref "R11") (pin "16") (pinfunction "16_16") (pintype "passive"))
    )
    (net (code "54") (name "/DIOD0") (class "Default")
      (node (ref "D25") (pin "3") (pinfunction "C_3") (pintype "passive"))
      (node (ref "J2") (pin "1") (pinfunction "1_1") (pintype "passive"))
      (node (ref "P1") (pin "49") (pinfunction "49_49") (pintype "passive"))
      (node (ref "P8") (pin "29") (pinfunction "29_29") (pintype "passive"))
      (node (ref "R7") (pin "9") (pinfunction "9_9") (pintype "passive"))
      (node (ref "U7") (pin "1") (pinfunction "~{A}_1") (pintype "input"))
      (node (ref "U8") (pin "2") (pinfunction "B_2") (pintype "input"))
    )
    (net (code "55") (name "/DIOD1") (class "Default")
      (node (ref "D26") (pin "3") (pinfunction "C_3") (pintype "passive"))
      (node (ref "P2") (pin "1") (pinfunction "1_1") (pintype "passive"))
      (node (ref "P8") (pin "63") (pinfunction "63_63") (pintype "passive"))
      (node (ref "R19") (pin "1") (pinfunction "1_1") (pintype "passive"))
      (node (ref "U9") (pin "12") (pinfunction "A_12") (pintype "input"))
      (node (ref "U9") (pin "13") (pinfunction "B_13") (pintype "input"))
    )
    (net (code "56") (name "/DIOD2") (class "Default")
      (node (ref "D27") (pin "3") (pinfunction "C_3") (pintype "passive"))
      (node (ref "P2") (pin "3") (pinfunction "3_3") (pintype "passive"))
      (node (ref "P8") (pin "64") (pinfunction "64_64") (pintype "passive"))
      (node (ref "R7") (pin "8") (pinfunction "8_8") (pintype "passive"))
      (node (ref "U4") (pin "7") (pinfunction "A5_7") (pintype "bidirectional"))
      (node (ref "U6") (pin "13") (pinfunction "P2_13") (pintype "input"))
    )
    (net (code "57") (name "/DIOD3") (class "Default")
      (node (ref "D28") (pin "3") (pinfunction "C_3") (pintype "passive"))
      (node (ref "P2") (pin "5") (pinfunction "5_5") (pintype "passive"))
      (node (ref "P8") (pin "31") (pinfunction "31_31") (pintype "passive"))
      (node (ref "R7") (pin "7") (pinfunction "7_7") (pintype "passive"))
      (node (ref "U4") (pin "6") (pinfunction "A4_6") (pintype "bidirectional"))
      (node (ref "U6") (pin "12") (pinfunction "P1_12") (pintype "input"))
    )
    (net (code "58") (name "/DIOD4") (class "Default")
      (node (ref "D29") (pin "3") (pinfunction "C_3") (pintype "passive"))
      (node (ref "P2") (pin "7") (pinfunction "7_7") (pintype "passive"))
      (node (ref "P8") (pin "32") (pinfunction "32_32") (pintype "passive"))
      (node (ref "R7") (pin "6") (pinfunction "6_6") (pintype "passive"))
      (node (ref "U4") (pin "5") (pinfunction "A3_5") (pintype "bidirectional"))
      (node (ref "U6") (pin "10") (pinfunction "P0_10") (pintype "input"))
    )
    (net (code "59") (name "/DIOD5") (class "Default")
      (node (ref "D30") (pin "3") (pinfunction "C_3") (pintype "passive"))
      (node (ref "P2") (pin "9") (pinfunction "9_9") (pintype "passive"))
      (node (ref "P8") (pin "66") (pinfunction "66_66") (pintype "passive"))
      (node (ref "R7") (pin "5") (pinfunction "5_5") (pintype "passive"))
      (node (ref "U4") (pin "4") (pinfunction "A2_4") (pintype "bidirectional"))
    )
    (net (code "60") (name "/DIOD6") (class "Default")
      (node (ref "D31") (pin "3") (pinfunction "C_3") (pintype "passive"))
      (node (ref "P2") (pin "11") (pinfunction "11_11") (pintype "passive"))
      (node (ref "P8") (pin "67") (pinfunction "67_67") (pintype "passive"))
      (node (ref "R7") (pin "4") (pinfunction "4_4") (pintype "passive"))
      (node (ref "U4") (pin "3") (pinfunction "A1_3") (pintype "bidirectional"))
    )
    (net (code "61") (name "/DIOD7") (class "Default")
      (node (ref "D32") (pin "3") (pinfunction "C_3") (pintype "passive"))
      (node (ref "P2") (pin "13") (pinfunction "13_13") (pintype "passive"))
      (node (ref "P8") (pin "34") (pinfunction "34_34") (pintype "passive"))
      (node (ref "R7") (pin "3") (pinfunction "3_3") (pintype "passive"))
      (node (ref "U4") (pin "2") (pinfunction "A0_2") (pintype "bidirectional"))
    )
    (net (code "62") (name "/DIOD10") (class "Default")
      (node (ref "P5") (pin "1") (pinfunction "1_1") (pintype "passive"))
      (node (ref "P7") (pin "1") (pinfunction "1_1") (pintype "passive"))
      (node (ref "R12") (pin "10") (pinfunction "10_10") (pintype "passive"))
    )
    (net (code "63") (name "/DIOD20") (class "Default")
      (node (ref "P5") (pin "3") (pinfunction "3_3") (pintype "passive"))
      (node (ref "P7") (pin "3") (pinfunction "3_3") (pintype "passive"))
      (node (ref "R12") (pin "11") (pinfunction "11_11") (pintype "passive"))
    )
    (net (code "64") (name "/DIOD30") (class "Default")
      (node (ref "P5") (pin "5") (pinfunction "5_5") (pintype "passive"))
      (node (ref "P7") (pin "5") (pinfunction "5_5") (pintype "passive"))
      (node (ref "R12") (pin "12") (pinfunction "12_12") (pintype "passive"))
    )
    (net (code "65") (name "/DIOD40") (class "Default")
      (node (ref "P5") (pin "7") (pinfunction "7_7") (pintype "passive"))
      (node (ref "P7") (pin "7") (pinfunction "7_7") (pintype "passive"))
      (node (ref "R12") (pin "13") (pinfunction "13_13") (pintype "passive"))
    )
    (net (code "66") (name "/DIOD50") (class "Default")
      (node (ref "P5") (pin "9") (pinfunction "9_9") (pintype "passive"))
      (node (ref "P7") (pin "9") (pinfunction "9_9") (pintype "passive"))
      (node (ref "R12") (pin "14") (pinfunction "14_14") (pintype "passive"))
    )
    (net (code "67") (name "/DIOD60") (class "Default")
      (node (ref "P5") (pin "11") (pinfunction "11_11") (pintype "passive"))
      (node (ref "P7") (pin "11") (pinfunction "11_11") (pintype "passive"))
      (node (ref "R12") (pin "15") (pinfunction "15_15") (pintype "passive"))
    )
    (net (code "68") (name "/DIOD70") (class "Default")
      (node (ref "P5") (pin "13") (pinfunction "13_13") (pintype "passive"))
      (node (ref "P7") (pin "13") (pinfunction "13_13") (pintype "passive"))
      (node (ref "R12") (pin "16") (pinfunction "16_16") (pintype "passive"))
    )
    (net (code "71") (name "/REQ1") (class "Default")
      (node (ref "P8") (pin "2") (pinfunction "2_2") (pintype "passive"))
      (node (ref "U5") (pin "11") (pinfunction "B7_11") (pintype "bidirectional"))
    )
    (net (code "73") (name "/START TRIG I") (class "Default")
      (node (ref "P3") (pin "3") (pinfunction "3_3") (pintype "passive"))
      (node (ref "R8") (pin "3") (pinfunction "3_3") (pintype "passive"))
      (node (ref "U5") (pin "8") (pinfunction "A6_8") (pintype "bidirectional"))
    )
    (net (code "76") (name "/Strobe") (class "Default")
      (node (ref "P4") (pin "49") (pinfunction "49_49") (pintype "passive"))
      (node (ref "R12") (pin "9") (pinfunction "9_9") (pintype "passive"))
    )
    (net (code "77") (name "GND") (class "Default")
      (node (ref "C10") (pin "1") (pinfunction "1_1") (pintype "passive"))
      (node (ref "C11") (pin "1") (pinfunction "1_1") (pintype "passive"))
      (node (ref "C12") (pin "1") (pinfunction "1_1") (pintype "passive"))
      (node (ref "C13") (pin "1") (pinfunction "1_1") (pintype "passive"))
      (node (ref "C14") (pin "1") (pinfunction "1_1") (pintype "passive"))
      (node (ref "C15") (pin "1") (pinfunction "1_1") (pintype "passive"))
      (node (ref "C16") (pin "2") (pinfunction "2_2") (pintype "passive"))
      (node (ref "C17") (pin "2") (pinfunction "2_2") (pintype "passive"))
      (node (ref "C18") (pin "2") (pinfunction "2_2") (pintype "passive"))
      (node (ref "C19") (pin "2") (pinfunction "2_2") (pintype "passive"))
      (node (ref "C20") (pin "2") (pinfunction "2_2") (pintype "passive"))
      (node (ref "C21") (pin "1") (pinfunction "1_1") (pintype "passive"))
      (node (ref "C22") (pin "2") (pinfunction "2_2") (pintype "passive"))
      (node (ref "C4") (pin "2") (pinfunction "2_2") (pintype "passive"))
      (node (ref "C5") (pin "1") (pinfunction "1_1") (pintype "passive"))
      (node (ref "C6") (pin "1") (pinfunction "1_1") (pintype "passive"))
      (node (ref "C7") (pin "1") (pinfunction "1_1") (pintype "passive"))
      (node (ref "C8") (pin "1") (pinfunction "1_1") (pintype "passive"))
      (node (ref "C9") (pin "1") (pinfunction "1_1") (pintype "passive"))
      (node (ref "D1") (pin "1") (pinfunction "A_1") (pintype "passive"))
      (node (ref "D10") (pin "1") (pinfunction "A_1") (pintype "passive"))
      (node (ref "D11") (pin "1") (pinfunction "A_1") (pintype "passive"))
      (node (ref "D12") (pin "1") (pinfunction "A_1") (pintype "passive"))
      (node (ref "D13") (pin "1") (pinfunction "A_1") (pintype "passive"))
      (node (ref "D14") (pin "1") (pinfunction "A_1") (pintype "passive"))
      (node (ref "D15") (pin "1") (pinfunction "A_1") (pintype "passive"))
      (node (ref "D16") (pin "1") (pinfunction "A_1") (pintype "passive"))
      (node (ref "D17") (pin "1") (pinfunction "A_1") (pintype "passive"))
      (node (ref "D18") (pin "1") (pinfunction "A_1") (pintype "passive"))
      (node (ref "D19") (pin "1") (pinfunction "A_1") (pintype "passive"))
      (node (ref "D2") (pin "1") (pinfunction "A_1") (pintype "passive"))
      (node (ref "D20") (pin "1") (pinfunction "A_1") (pintype "passive"))
      (node (ref "D21") (pin "1") (pinfunction "A_1") (pintype "passive"))
      (node (ref "D22") (pin "1") (pinfunction "A_1") (pintype "passive"))
      (node (ref "D23") (pin "1") (pinfunction "A_1") (pintype "passive"))
      (node (ref "D24") (pin "1") (pinfunction "A_1") (pintype "passive"))
      (node (ref "D25") (pin "1") (pinfunction "A_1") (pintype "passive"))
      (node (ref "D26") (pin "1") (pinfunction "A_1") (pintype "passive"))
      (node (ref "D27") (pin "1") (pinfunction "A_1") (pintype "passive"))
      (node (ref "D28") (pin "1") (pinfunction "A_1") (pintype "passive"))
      (node (ref "D29") (pin "1") (pinfunction "A_1") (pintype "passive"))
      (node (ref "D3") (pin "1") (pinfunction "A_1") (pintype "passive"))
      (node (ref "D30") (pin "1") (pinfunction "A_1") (pintype "passive"))
      (node (ref "D31") (pin "1") (pinfunction "A_1") (pintype "passive"))
      (node (ref "D32") (pin "1") (pinfunction "A_1") (pintype "passive"))
      (node (ref "D4") (pin "1") (pinfunction "A_1") (pintype "passive"))
      (node (ref "D5") (pin "1") (pinfunction "A_1") (pintype "passive"))
      (node (ref "D6") (pin "1") (pinfunction "A_1") (pintype "passive"))
      (node (ref "D7") (pin "1") (pinfunction "A_1") (pintype "passive"))
      (node (ref "D8") (pin "1") (pinfunction "A_1") (pintype "passive"))
      (node (ref "D9") (pin "1") (pinfunction "A_1") (pintype "passive"))
      (node (ref "J1") (pin "1") (pinfunction "1_1") (pintype "passive"))
      (node (ref "J4") (pin "2") (pinfunction "2_2") (pintype "passive"))
      (node (ref "P1") (pin "10") (pinfunction "10_10") (pintype "passive"))
      (node (ref "P1") (pin "12") (pinfunction "12_12") (pintype "passive"))
      (node (ref "P1") (pin "14") (pinfunction "14_14") (pintype "passive"))
      (node (ref "P1") (pin "16") (pinfunction "16_16") (pintype "passive"))
      (node (ref "P1") (pin "18") (pinfunction "18_18") (pintype "passive"))
      (node (ref "P1") (pin "2") (pinfunction "2_2") (pintype "passive"))
      (node (ref "P1") (pin "20") (pinfunction "20_20") (pintype "passive"))
      (node (ref "P1") (pin "22") (pinfunction "22_22") (pintype "passive"))
      (node (ref "P1") (pin "24") (pinfunction "24_24") (pintype "passive"))
      (node (ref "P1") (pin "26") (pinfunction "26_26") (pintype "passive"))
      (node (ref "P1") (pin "28") (pinfunction "28_28") (pintype "passive"))
      (node (ref "P1") (pin "30") (pinfunction "30_30") (pintype "passive"))
      (node (ref "P1") (pin "32") (pinfunction "32_32") (pintype "passive"))
      (node (ref "P1") (pin "34") (pinfunction "34_34") (pintype "passive"))
      (node (ref "P1") (pin "36") (pinfunction "36_36") (pintype "passive"))
      (node (ref "P1") (pin "38") (pinfunction "38_38") (pintype "passive"))
      (node (ref "P1") (pin "4") (pinfunction "4_4") (pintype "passive"))
      (node (ref "P1") (pin "40") (pinfunction "40_40") (pintype "passive"))
      (node (ref "P1") (pin "42") (pinfunction "42_42") (pintype "passive"))
      (node (ref "P1") (pin "44") (pinfunction "44_44") (pintype "passive"))
      (node (ref "P1") (pin "46") (pinfunction "46_46") (pintype "passive"))
      (node (ref "P1") (pin "48") (pinfunction "48_48") (pintype "passive"))
      (node (ref "P1") (pin "50") (pinfunction "50_50") (pintype "passive"))
      (node (ref "P1") (pin "6") (pinfunction "6_6") (pintype "passive"))
      (node (ref "P1") (pin "8") (pinfunction "8_8") (pintype "passive"))
      (node (ref "P11") (pin "1") (pinfunction "1_1") (pintype "passive"))
      (node (ref "P2") (pin "10") (pinfunction "10_10") (pintype "passive"))
      (node (ref "P2") (pin "12") (pinfunction "12_12") (pintype "passive"))
      (node (ref "P2") (pin "14") (pinfunction "14_14") (pintype "passive"))
      (node (ref "P2") (pin "15") (pinfunction "15_15") (pintype "passive"))
      (node (ref "P2") (pin "16") (pinfunction "16_16") (pintype "passive"))
      (node (ref "P2") (pin "2") (pinfunction "2_2") (pintype "passive"))
      (node (ref "P2") (pin "4") (pinfunction "4_4") (pintype "passive"))
      (node (ref "P2") (pin "6") (pinfunction "6_6") (pintype "passive"))
      (node (ref "P2") (pin "8") (pinfunction "8_8") (pintype "passive"))
      (node (ref "P3") (pin "10") (pinfunction "10_10") (pintype "passive"))
      (node (ref "P3") (pin "12") (pinfunction "12_12") (pintype "passive"))
      (node (ref "P3") (pin "14") (pinfunction "14_14") (pintype "passive"))
      (node (ref "P3") (pin "16") (pinfunction "16_16") (pintype "passive"))
      (node (ref "P3") (pin "2") (pinfunction "2_2") (pintype "passive"))
      (node (ref "P3") (pin "4") (pinfunction "4_4") (pintype "passive"))
      (node (ref "P3") (pin "6") (pinfunction "6_6") (pintype "passive"))
      (node (ref "P3") (pin "8") (pinfunction "8_8") (pintype "passive"))
      (node (ref "P4") (pin "12") (pinfunction "12_12") (pintype "passive"))
      (node (ref "P4") (pin "14") (pinfunction "14_14") (pintype "passive"))
      (node (ref "P4") (pin "16") (pinfunction "16_16") (pintype "passive"))
      (node (ref "P4") (pin "18") (pinfunction "18_18") (pintype "passive"))
      (node (ref "P4") (pin "20") (pinfunction "20_20") (pintype "passive"))
      (node (ref "P4") (pin "22") (pinfunction "22_22") (pintype "passive"))
      (node (ref "P4") (pin "24") (pinfunction "24_24") (pintype "passive"))
      (node (ref "P4") (pin "26") (pinfunction "26_26") (pintype "passive"))
      (node (ref "P4") (pin "28") (pinfunction "28_28") (pintype "passive"))
      (node (ref "P4") (pin "30") (pinfunction "30_30") (pintype "passive"))
      (node (ref "P4") (pin "32") (pinfunction "32_32") (pintype "passive"))
      (node (ref "P4") (pin "34") (pinfunction "34_34") (pintype "passive"))
      (node (ref "P4") (pin "36") (pinfunction "36_36") (pintype "passive"))
      (node (ref "P4") (pin "38") (pinfunction "38_38") (pintype "passive"))
      (node (ref "P4") (pin "40") (pinfunction "40_40") (pintype "passive"))
      (node (ref "P4") (pin "42") (pinfunction "42_42") (pintype "passive"))
      (node (ref "P4") (pin "44") (pinfunction "44_44") (pintype "passive"))
      (node (ref "P4") (pin "46") (pinfunction "46_46") (pintype "passive"))
      (node (ref "P4") (pin "48") (pinfunction "48_48") (pintype "passive"))
      (node (ref "P4") (pin "50") (pinfunction "50_50") (pintype "passive"))
      (node (ref "P5") (pin "10") (pinfunction "10_10") (pintype "passive"))
      (node (ref "P5") (pin "12") (pinfunction "12_12") (pintype "passive"))
      (node (ref "P5") (pin "14") (pinfunction "14_14") (pintype "passive"))
      (node (ref "P5") (pin "15") (pinfunction "15_15") (pintype "passive"))
      (node (ref "P5") (pin "16") (pinfunction "16_16") (pintype "passive"))
      (node (ref "P5") (pin "2") (pinfunction "2_2") (pintype "passive"))
      (node (ref "P5") (pin "4") (pinfunction "4_4") (pintype "passive"))
      (node (ref "P5") (pin "6") (pinfunction "6_6") (pintype "passive"))
      (node (ref "P5") (pin "8") (pinfunction "8_8") (pintype "passive"))
      (node (ref "P7") (pin "10") (pinfunction "10_10") (pintype "passive"))
      (node (ref "P7") (pin "12") (pinfunction "12_12") (pintype "passive"))
      (node (ref "P7") (pin "14") (pinfunction "14_14") (pintype "passive"))
      (node (ref "P7") (pin "15") (pinfunction "15_15") (pintype "passive"))
      (node (ref "P7") (pin "16") (pinfunction "16_16") (pintype "passive"))
      (node (ref "P7") (pin "2") (pinfunction "2_2") (pintype "passive"))
      (node (ref "P7") (pin "4") (pinfunction "4_4") (pintype "passive"))
      (node (ref "P7") (pin "6") (pinfunction "6_6") (pintype "passive"))
      (node (ref "P7") (pin "8") (pinfunction "8_8") (pintype "passive"))
      (node (ref "P8") (pin "11") (pinfunction "11_11") (pintype "passive"))
      (node (ref "P8") (pin "14") (pinfunction "14_14") (pintype "passive"))
      (node (ref "P8") (pin "18") (pinfunction "18_18") (pintype "passive"))
      (node (ref "P8") (pin "19") (pinfunction "19_19") (pintype "passive"))
      (node (ref "P8") (pin "20") (pinfunction "20_20") (pintype "passive"))
      (node (ref "P8") (pin "24") (pinfunction "24_24") (pintype "passive"))
      (node (ref "P8") (pin "27") (pinfunction "27_27") (pintype "passive"))
      (node (ref "P8") (pin "30") (pinfunction "30_30") (pintype "passive"))
      (node (ref "P8") (pin "33") (pinfunction "33_33") (pintype "passive"))
      (node (ref "P8") (pin "35") (pinfunction "35_35") (pintype "passive"))
      (node (ref "P8") (pin "36") (pinfunction "36_36") (pintype "passive"))
      (node (ref "P8") (pin "37") (pinfunction "37_37") (pintype "passive"))
      (node (ref "P8") (pin "39") (pinfunction "39_39") (pintype "passive"))
      (node (ref "P8") (pin "41") (pinfunction "41_41") (pintype "passive"))
      (node (ref "P8") (pin "42") (pinfunction "42_42") (pintype "passive"))
      (node (ref "P8") (pin "43") (pinfunction "43_43") (pintype "passive"))
      (node (ref "P8") (pin "46") (pinfunction "46_46") (pintype "passive"))
      (node (ref "P8") (pin "49") (pinfunction "49_49") (pintype "passive"))
      (node (ref "P8") (pin "50") (pinfunction "50_50") (pintype "passive"))
      (node (ref "P8") (pin "55") (pinfunction "55_55") (pintype "passive"))
      (node (ref "P8") (pin "56") (pinfunction "56_56") (pintype "passive"))
      (node (ref "P8") (pin "59") (pinfunction "59_59") (pintype "passive"))
      (node (ref "P8") (pin "62") (pinfunction "62_62") (pintype "passive"))
      (node (ref "P8") (pin "65") (pinfunction "65_65") (pintype "passive"))
      (node (ref "P8") (pin "68") (pinfunction "68_68") (pintype "passive"))
      (node (ref "P9") (pin "8") (pinfunction "8_8") (pintype "passive"))
      (node (ref "R1") (pin "1") (pinfunction "1_1") (pintype "passive"))
      (node (ref "R2") (pin "1") (pinfunction "1_1") (pintype "passive"))
      (node (ref "R3") (pin "1") (pinfunction "1_1") (pintype "passive"))
      (node (ref "R4") (pin "1") (pinfunction "1_1") (pintype "passive"))
      (node (ref "R5") (pin "1") (pinfunction "1_1") (pintype "passive"))
      (node (ref "R6") (pin "1") (pinfunction "1_1") (pintype "passive"))
      (node (ref "R7") (pin "1") (pinfunction "1_1") (pintype "passive"))
      (node (ref "R8") (pin "1") (pinfunction "1_1") (pintype "passive"))
      (node (ref "U1") (pin "10") (pinfunction "GND_10") (pintype "power_in"))
      (node (ref "U1") (pin "19") (pinfunction "~{OE}_19") (pintype "input"))
      (node (ref "U2") (pin "10") (pinfunction "GND_10") (pintype "power_in"))
      (node (ref "U2") (pin "19") (pinfunction "~{OE}_19") (pintype "input"))
      (node (ref "U3") (pin "10") (pinfunction "GND_10") (pintype "power_in"))
      (node (ref "U3") (pin "19") (pinfunction "~{OE}_19") (pintype "input"))
      (node (ref "U4") (pin "10") (pinfunction "GND_10") (pintype "power_in"))
      (node (ref "U4") (pin "19") (pinfunction "~{OE}_19") (pintype "input"))
      (node (ref "U5") (pin "10") (pinfunction "GND_10") (pintype "power_in"))
      (node (ref "U5") (pin "19") (pinfunction "~{OE}_19") (pintype "input"))
      (node (ref "U6") (pin "1") (pinfunction "Q3_1") (pintype "input"))
      (node (ref "U6") (pin "15") (pinfunction "P3_15") (pintype "input"))
      (node (ref "U6") (pin "2") (pinfunction "P<Qin_2") (pintype "input"))
      (node (ref "U6") (pin "4") (pinfunction "P>Qin_4") (pintype "input"))
      (node (ref "U6") (pin "8") (pinfunction "GND_8") (pintype "power_in"))
      (node (ref "U7") (pin "8") (pinfunction "GND_8") (pintype "power_in"))
      (node (ref "U8") (pin "1") (pinfunction "~{A}_1") (pintype "input"))
      (node (ref "U8") (pin "10") (pinfunction "B_10") (pintype "input"))
      (node (ref "U8") (pin "11") (pinfunction "~{CLR}_11") (pintype "input"))
      (node (ref "U8") (pin "8") (pinfunction "GND_8") (pintype "power_in"))
      (node (ref "U8") (pin "9") (pinfunction "~{A}_9") (pintype "input"))
      (node (ref "U9") (pin "7") (pinfunction "GND_7") (pintype "power_in"))
    )
    (net (code "78") (name "Net-(J1-Pad2)") (class "Default")
      (node (ref "J1") (pin "2") (pinfunction "2_2") (pintype "passive"))
      (node (ref "P4") (pin "10") (pinfunction "10_10") (pintype "passive"))
      (node (ref "P4") (pin "2") (pinfunction "2_2") (pintype "passive"))
      (node (ref "P4") (pin "4") (pinfunction "4_4") (pintype "passive"))
      (node (ref "P4") (pin "6") (pinfunction "6_6") (pintype "passive"))
      (node (ref "P4") (pin "8") (pinfunction "8_8") (pintype "passive"))
      (node (ref "P6") (pin "10") (pinfunction "10_10") (pintype "passive"))
      (node (ref "P6") (pin "2") (pinfunction "2_2") (pintype "passive"))
      (node (ref "P6") (pin "4") (pinfunction "4_4") (pintype "passive"))
      (node (ref "P6") (pin "6") (pinfunction "6_6") (pintype "passive"))
      (node (ref "P6") (pin "8") (pinfunction "8_8") (pintype "passive"))
    )
    (net (code "79") (name "Net-(J4-Pad1)") (class "Default")
      (node (ref "J4") (pin "1") (pinfunction "1_1") (pintype "passive"))
      (node (ref "P6") (pin "12") (pinfunction "12_12") (pintype "passive"))
      (node (ref "P6") (pin "14") (pinfunction "14_14") (pintype "passive"))
      (node (ref "P6") (pin "16") (pinfunction "16_16") (pintype "passive"))
      (node (ref "P6") (pin "18") (pinfunction "18_18") (pintype "passive"))
      (node (ref "P6") (pin "20") (pinfunction "20_20") (pintype "passive"))
      (node (ref "P6") (pin "22") (pinfunction "22_22") (pintype "passive"))
      (node (ref "P6") (pin "24") (pinfunction "24_24") (pintype "passive"))
      (node (ref "P6") (pin "26") (pinfunction "26_26") (pintype "passive"))
      (node (ref "P6") (pin "28") (pinfunction "28_28") (pintype "passive"))
      (node (ref "P6") (pin "30") (pinfunction "30_30") (pintype "passive"))
      (node (ref "P6") (pin "32") (pinfunction "32_32") (pintype "passive"))
      (node (ref "P6") (pin "34") (pinfunction "34_34") (pintype "passive"))
      (node (ref "P6") (pin "36") (pinfunction "36_36") (pintype "passive"))
      (node (ref "P6") (pin "38") (pinfunction "38_38") (pintype "passive"))
      (node (ref "P6") (pin "40") (pinfunction "40_40") (pintype "passive"))
      (node (ref "P6") (pin "42") (pinfunction "42_42") (pintype "passive"))
      (node (ref "P6") (pin "44") (pinfunction "44_44") (pintype "passive"))
      (node (ref "P6") (pin "46") (pinfunction "46_46") (pintype "passive"))
      (node (ref "P6") (pin "48") (pinfunction "48_48") (pintype "passive"))
      (node (ref "P6") (pin "50") (pinfunction "50_50") (pintype "passive"))
    )
    (net (code "80") (name "Net-(R13-BOT)") (class "Default")
      (node (ref "C1") (pin "2") (pinfunction "2_2") (pintype "passive"))
      (node (ref "R13") (pin "1") (pinfunction "BOT_1") (pintype "passive"))
      (node (ref "U7") (pin "7") (pinfunction "CX/RX_7") (pintype "passive"))
    )
    (net (code "81") (name "Net-(R14-BOT)") (class "Default")
      (node (ref "C2") (pin "2") (pinfunction "2_2") (pintype "passive"))
      (node (ref "R14") (pin "1") (pinfunction "BOT_1") (pintype "passive"))
      (node (ref "U7") (pin "15") (pinfunction "CX/RX_15") (pintype "passive"))
    )
    (net (code "82") (name "Net-(R15-BOT)") (class "Default")
      (node (ref "C3") (pin "1") (pinfunction "1_1") (pintype "passive"))
      (node (ref "R15") (pin "1") (pinfunction "BOT_1") (pintype "passive"))
      (node (ref "U8") (pin "15") (pinfunction "CX/RX_15") (pintype "passive"))
    )
    (net (code "83") (name "Net-(S1-B1)") (class "Default")
      (node (ref "R3") (pin "2") (pinfunction "2_2") (pintype "passive"))
      (node (ref "S1") (pin "6") (pinfunction "B1_6") (pintype "passive"))
      (node (ref "U6") (pin "14") (pinfunction "Q2_14") (pintype "input"))
    )
    (net (code "84") (name "Net-(S1-B2)") (class "Default")
      (node (ref "R2") (pin "2") (pinfunction "2_2") (pintype "passive"))
      (node (ref "S1") (pin "5") (pinfunction "B2_5") (pintype "passive"))
      (node (ref "U6") (pin "11") (pinfunction "Q1_11") (pintype "input"))
    )
    (net (code "85") (name "Net-(S1-B3)") (class "Default")
      (node (ref "R1") (pin "2") (pinfunction "2_2") (pintype "passive"))
      (node (ref "S1") (pin "4") (pinfunction "B3_4") (pintype "passive"))
      (node (ref "U6") (pin "9") (pinfunction "Q0_9") (pintype "input"))
    )
    (net (code "86") (name "Net-(U1-B0)") (class "Default")
      (node (ref "R9") (pin "1") (pinfunction "1_1") (pintype "passive"))
      (node (ref "U1") (pin "18") (pinfunction "B0_18") (pintype "bidirectional"))
    )
    (net (code "87") (name "Net-(U1-B1)") (class "Default")
      (node (ref "R9") (pin "2") (pinfunction "2_2") (pintype "passive"))
      (node (ref "U1") (pin "17") (pinfunction "B1_17") (pintype "bidirectional"))
    )
    (net (code "88") (name "Net-(U1-B2)") (class "Default")
      (node (ref "R9") (pin "3") (pinfunction "3_3") (pintype "passive"))
      (node (ref "U1") (pin "16") (pinfunction "B2_16") (pintype "bidirectional"))
    )
    (net (code "89") (name "Net-(U1-B3)") (class "Default")
      (node (ref "R9") (pin "4") (pinfunction "4_4") (pintype "passive"))
      (node (ref "U1") (pin "15") (pinfunction "B3_15") (pintype "bidirectional"))
    )
    (net (code "90") (name "Net-(U1-B4)") (class "Default")
      (node (ref "R9") (pin "5") (pinfunction "5_5") (pintype "passive"))
      (node (ref "U1") (pin "14") (pinfunction "B4_14") (pintype "bidirectional"))
    )
    (net (code "91") (name "Net-(U1-B5)") (class "Default")
      (node (ref "R9") (pin "6") (pinfunction "6_6") (pintype "passive"))
      (node (ref "U1") (pin "13") (pinfunction "B5_13") (pintype "bidirectional"))
    )
    (net (code "92") (name "Net-(U1-B6)") (class "Default")
      (node (ref "R9") (pin "7") (pinfunction "7_7") (pintype "passive"))
      (node (ref "U1") (pin "12") (pinfunction "B6_12") (pintype "bidirectional"))
    )
    (net (code "93") (name "Net-(U1-B7)") (class "Default")
      (node (ref "R9") (pin "8") (pinfunction "8_8") (pintype "passive"))
      (node (ref "U1") (pin "11") (pinfunction "B7_11") (pintype "bidirectional"))
    )
    (net (code "94") (name "Net-(U1-T{slash}~{R})") (class "Default")
      (node (ref "U1") (pin "1") (pinfunction "T/~{R}_1") (pintype "input"))
      (node (ref "U2") (pin "1") (pinfunction "T/~{R}_1") (pintype "input"))
      (node (ref "U4") (pin "8") (pinfunction "A6_8") (pintype "bidirectional"))
      (node (ref "U9") (pin "8") (pinfunction "Y_8") (pintype "output"))
    )
    (net (code "95") (name "Net-(U2-B0)") (class "Default")
      (node (ref "R10") (pin "1") (pinfunction "1_1") (pintype "passive"))
      (node (ref "U2") (pin "18") (pinfunction "B0_18") (pintype "bidirectional"))
    )
    (net (code "96") (name "Net-(U2-B1)") (class "Default")
      (node (ref "R10") (pin "2") (pinfunction "2_2") (pintype "passive"))
      (node (ref "U2") (pin "17") (pinfunction "B1_17") (pintype "bidirectional"))
    )
    (net (code "97") (name "Net-(U2-B2)") (class "Default")
      (node (ref "R10") (pin "3") (pinfunction "3_3") (pintype "passive"))
      (node (ref "U2") (pin "16") (pinfunction "B2_16") (pintype "bidirectional"))
    )
    (net (code "98") (name "Net-(U2-B3)") (class "Default")
      (node (ref "R10") (pin "4") (pinfunction "4_4") (pintype "passive"))
      (node (ref "U2") (pin "15") (pinfunction "B3_15") (pintype "bidirectional"))
    )
    (net (code "99") (name "Net-(U2-B4)") (class "Default")
      (node (ref "R10") (pin "5") (pinfunction "5_5") (pintype "passive"))
      (node (ref "U2") (pin "14") (pinfunction "B4_14") (pintype "bidirectional"))
    )
    (net (code "100") (name "Net-(U2-B5)") (class "Default")
      (node (ref "R10") (pin "6") (pinfunction "6_6") (pintype "passive"))
      (node (ref "U2") (pin "13") (pinfunction "B5_13") (pintype "bidirectional"))
    )
    (net (code "101") (name "Net-(U2-B6)") (class "Default")
      (node (ref "R10") (pin "7") (pinfunction "7_7") (pintype "passive"))
      (node (ref "U2") (pin "12") (pinfunction "B6_12") (pintype "bidirectional"))
    )
    (net (code "102") (name "Net-(U2-B7)") (class "Default")
      (node (ref "R10") (pin "8") (pinfunction "8_8") (pintype "passive"))
      (node (ref "U2") (pin "11") (pinfunction "B7_11") (pintype "bidirectional"))
    )
    (net (code "103") (name "Net-(U3-B0)") (class "Default")
      (node (ref "R11") (pin "1") (pinfunction "1_1") (pintype "passive"))
      (node (ref "U3") (pin "18") (pinfunction "B0_18") (pintype "bidirectional"))
    )
    (net (code "104") (name "Net-(U3-B1)") (class "Default")
      (node (ref "R11") (pin "2") (pinfunction "2_2") (pintype "passive"))
      (node (ref "U3") (pin "17") (pinfunction "B1_17") (pintype "bidirectional"))
    )
    (net (code "105") (name "Net-(U3-B2)") (class "Default")
      (node (ref "R11") (pin "3") (pinfunction "3_3") (pintype "passive"))
      (node (ref "U3") (pin "16") (pinfunction "B2_16") (pintype "bidirectional"))
    )
    (net (code "106") (name "Net-(U3-B3)") (class "Default")
      (node (ref "R11") (pin "4") (pinfunction "4_4") (pintype "passive"))
      (node (ref "U3") (pin "15") (pinfunction "B3_15") (pintype "bidirectional"))
    )
    (net (code "107") (name "Net-(U3-B4)") (class "Default")
      (node (ref "R11") (pin "5") (pinfunction "5_5") (pintype "passive"))
      (node (ref "U3") (pin "14") (pinfunction "B4_14") (pintype "bidirectional"))
    )
    (net (code "108") (name "Net-(U3-B5)") (class "Default")
      (node (ref "R11") (pin "6") (pinfunction "6_6") (pintype "passive"))
      (node (ref "U3") (pin "13") (pinfunction "B5_13") (pintype "bidirectional"))
    )
    (net (code "109") (name "Net-(U3-B6)") (class "Default")
      (node (ref "R11") (pin "7") (pinfunction "7_7") (pintype "passive"))
      (node (ref "U3") (pin "12") (pinfunction "B6_12") (pintype "bidirectional"))
    )
    (net (code "110") (name "Net-(U3-B7)") (class "Default")
      (node (ref "R11") (pin "8") (pinfunction "8_8") (pintype "passive"))
      (node (ref "U3") (pin "11") (pinfunction "B7_11") (pintype "bidirectional"))
    )
    (net (code "111") (name "Net-(U4-A7)") (class "Default")
      (node (ref "J3") (pin "2") (pinfunction "2_2") (pintype "passive"))
      (node (ref "U4") (pin "9") (pinfunction "A7_9") (pintype "bidirectional"))
      (node (ref "U9") (pin "9") (pinfunction "A_9") (pintype "input"))
    )
    (net (code "112") (name "Net-(U4-B0)") (class "Default")
      (node (ref "R12") (pin "1") (pinfunction "1_1") (pintype "passive"))
      (node (ref "U4") (pin "18") (pinfunction "B0_18") (pintype "bidirectional"))
    )
    (net (code "113") (name "Net-(U4-B1)") (class "Default")
      (node (ref "R12") (pin "2") (pinfunction "2_2") (pintype "passive"))
      (node (ref "U4") (pin "17") (pinfunction "B1_17") (pintype "bidirectional"))
    )
    (net (code "114") (name "Net-(U4-B2)") (class "Default")
      (node (ref "R12") (pin "3") (pinfunction "3_3") (pintype "passive"))
      (node (ref "U4") (pin "16") (pinfunction "B2_16") (pintype "bidirectional"))
    )
    (net (code "115") (name "Net-(U4-B3)") (class "Default")
      (node (ref "R12") (pin "4") (pinfunction "4_4") (pintype "passive"))
      (node (ref "U4") (pin "15") (pinfunction "B3_15") (pintype "bidirectional"))
    )
    (net (code "116") (name "Net-(U4-B4)") (class "Default")
      (node (ref "R12") (pin "5") (pinfunction "5_5") (pintype "passive"))
      (node (ref "U4") (pin "14") (pinfunction "B4_14") (pintype "bidirectional"))
    )
    (net (code "117") (name "Net-(U4-B5)") (class "Default")
      (node (ref "R12") (pin "6") (pinfunction "6_6") (pintype "passive"))
      (node (ref "U4") (pin "13") (pinfunction "B5_13") (pintype "bidirectional"))
    )
    (net (code "118") (name "Net-(U4-B6)") (class "Default")
      (node (ref "R12") (pin "7") (pinfunction "7_7") (pintype "passive"))
      (node (ref "U4") (pin "12") (pinfunction "B6_12") (pintype "bidirectional"))
    )
    (net (code "119") (name "Net-(U4-B7)") (class "Default")
      (node (ref "R12") (pin "8") (pinfunction "8_8") (pintype "passive"))
      (node (ref "U4") (pin "11") (pinfunction "B7_11") (pintype "bidirectional"))
    )
    (net (code "120") (name "Net-(U5-A0)") (class "Default")
      (node (ref "P3") (pin "15") (pinfunction "15_15") (pintype "passive"))
      (node (ref "R8") (pin "9") (pinfunction "9_9") (pintype "passive"))
      (node (ref "U5") (pin "2") (pinfunction "A0_2") (pintype "bidirectional"))
    )
    (net (code "121") (name "Net-(U5-A1)") (class "Default")
      (node (ref "P3") (pin "13") (pinfunction "13_13") (pintype "passive"))
      (node (ref "R8") (pin "8") (pinfunction "8_8") (pintype "passive"))
      (node (ref "U5") (pin "3") (pinfunction "A1_3") (pintype "bidirectional"))
    )
    (net (code "122") (name "Net-(U5-A2)") (class "Default")
      (node (ref "P3") (pin "11") (pinfunction "11_11") (pintype "passive"))
      (node (ref "R8") (pin "7") (pinfunction "7_7") (pintype "passive"))
      (node (ref "U5") (pin "4") (pinfunction "A2_4") (pintype "bidirectional"))
    )
    (net (code "123") (name "Net-(U5-A3)") (class "Default")
      (node (ref "P3") (pin "9") (pinfunction "9_9") (pintype "passive"))
      (node (ref "R8") (pin "6") (pinfunction "6_6") (pintype "passive"))
      (node (ref "U5") (pin "5") (pinfunction "A3_5") (pintype "bidirectional"))
    )
    (net (code "124") (name "Net-(U5-A4)") (class "Default")
      (node (ref "P3") (pin "7") (pinfunction "7_7") (pintype "passive"))
      (node (ref "R8") (pin "5") (pinfunction "5_5") (pintype "passive"))
      (node (ref "U5") (pin "6") (pinfunction "A4_6") (pintype "bidirectional"))
    )
    (net (code "125") (name "Net-(U5-A5)") (class "Default")
      (node (ref "P3") (pin "5") (pinfunction "5_5") (pintype "passive"))
      (node (ref "R8") (pin "4") (pinfunction "4_4") (pintype "passive"))
      (node (ref "U5") (pin "7") (pinfunction "A5_7") (pintype "bidirectional"))
    )
    (net (code "126") (name "Net-(U6-P=Qin)") (class "Default")
      (node (ref "J2") (pin "2") (pinfunction "2_2") (pintype "passive"))
      (node (ref "J3") (pin "1") (pinfunction "1_1") (pintype "passive"))
      (node (ref "U6") (pin "3") (pinfunction "P=Qin_3") (pintype "input"))
    )
    (net (code "127") (name "Net-(U6-P=Qout)") (class "Default")
      (node (ref "J3") (pin "3") (pinfunction "3_3") (pintype "passive"))
      (node (ref "U6") (pin "6") (pinfunction "P=Qout_6") (pintype "output"))
    )
    (net (code "128") (name "Net-(U7A-CX)") (class "Default")
      (node (ref "C2") (pin "1") (pinfunction "1_1") (pintype "passive"))
      (node (ref "U7") (pin "14") (pinfunction "CX_14") (pintype "passive"))
    )
    (net (code "129") (name "Net-(U7A-Q)") (class "Default")
      (node (ref "U7") (pin "13") (pinfunction "Q_13") (pintype "output"))
      (node (ref "U7") (pin "9") (pinfunction "~{A}_9") (pintype "input"))
    )
    (net (code "130") (name "Net-(U7B-B)") (class "Default")
      (node (ref "U7") (pin "10") (pinfunction "B_10") (pintype "input"))
      (node (ref "U8") (pin "4") (pinfunction "~{Q}_4") (pintype "output"))
    )
    (net (code "131") (name "Net-(U7B-CX)") (class "Default")
      (node (ref "C1") (pin "1") (pinfunction "1_1") (pintype "passive"))
      (node (ref "U7") (pin "6") (pinfunction "CX_6") (pintype "passive"))
    )
    (net (code "132") (name "Net-(U7B-Q)") (class "Default")
      (node (ref "J2") (pin "3") (pinfunction "3_3") (pintype "passive"))
      (node (ref "U7") (pin "5") (pinfunction "Q_5") (pintype "output"))
    )
    (net (code "133") (name "Net-(U8A-CX)") (class "Default")
      (node (ref "C3") (pin "2") (pinfunction "2_2") (pintype "passive"))
      (node (ref "U8") (pin "14") (pinfunction "CX_14") (pintype "passive"))
    )
    (net (code "134") (name "Net-(U9C-B)") (class "Default")
      (node (ref "U9") (pin "10") (pinfunction "B_10") (pintype "input"))
      (node (ref "U9") (pin "11") (pinfunction "Y_11") (pintype "output"))
    )
    (net (code "135") (name "VCC") (class "Default")
      (node (ref "C10") (pin "2") (pinfunction "2_2") (pintype "passive"))
      (node (ref "C11") (pin "2") (pinfunction "2_2") (pintype "passive"))
      (node (ref "C12") (pin "2") (pinfunction "2_2") (pintype "passive"))
      (node (ref "C13") (pin "2") (pinfunction "2_2") (pintype "passive"))
      (node (ref "C14") (pin "2") (pinfunction "2_2") (pintype "passive"))
      (node (ref "C15") (pin "2") (pinfunction "2_2") (pintype "passive"))
      (node (ref "C16") (pin "1") (pinfunction "1_1") (pintype "passive"))
      (node (ref "C17") (pin "1") (pinfunction "1_1") (pintype "passive"))
      (node (ref "C18") (pin "1") (pinfunction "1_1") (pintype "passive"))
      (node (ref "C19") (pin "1") (pinfunction "1_1") (pintype "passive"))
      (node (ref "C20") (pin "1") (pinfunction "1_1") (pintype "passive"))
      (node (ref "C21") (pin "2") (pinfunction "2_2") (pintype "passive"))
      (node (ref "C4") (pin "1") (pinfunction "1_1") (pintype "passive"))
      (node (ref "C5") (pin "2") (pinfunction "2_2") (pintype "passive"))
      (node (ref "C6") (pin "2") (pinfunction "2_2") (pintype "passive"))
      (node (ref "C7") (pin "2") (pinfunction "2_2") (pintype "passive"))
      (node (ref "C8") (pin "2") (pinfunction "2_2") (pintype "passive"))
      (node (ref "C9") (pin "2") (pinfunction "2_2") (pintype "passive"))
      (node (ref "D1") (pin "2") (pinfunction "K_2") (pintype "passive"))
      (node (ref "D10") (pin "2") (pinfunction "K_2") (pintype "passive"))
      (node (ref "D11") (pin "2") (pinfunction "K_2") (pintype "passive"))
      (node (ref "D12") (pin "2") (pinfunction "K_2") (pintype "passive"))
      (node (ref "D13") (pin "2") (pinfunction "K_2") (pintype "passive"))
      (node (ref "D14") (pin "2") (pinfunction "K_2") (pintype "passive"))
      (node (ref "D15") (pin "2") (pinfunction "K_2") (pintype "passive"))
      (node (ref "D16") (pin "2") (pinfunction "K_2") (pintype "passive"))
      (node (ref "D17") (pin "2") (pinfunction "K_2") (pintype "passive"))
      (node (ref "D18") (pin "2") (pinfunction "K_2") (pintype "passive"))
      (node (ref "D19") (pin "2") (pinfunction "K_2") (pintype "passive"))
      (node (ref "D2") (pin "2") (pinfunction "K_2") (pintype "passive"))
      (node (ref "D20") (pin "2") (pinfunction "K_2") (pintype "passive"))
      (node (ref "D21") (pin "2") (pinfunction "K_2") (pintype "passive"))
      (node (ref "D22") (pin "2") (pinfunction "K_2") (pintype "passive"))
      (node (ref "D23") (pin "2") (pinfunction "K_2") (pintype "passive"))
      (node (ref "D24") (pin "2") (pinfunction "K_2") (pintype "passive"))
      (node (ref "D25") (pin "2") (pinfunction "K_2") (pintype "passive"))
      (node (ref "D26") (pin "2") (pinfunction "K_2") (pintype "passive"))
      (node (ref "D27") (pin "2") (pinfunction "K_2") (pintype "passive"))
      (node (ref "D28") (pin "2") (pinfunction "K_2") (pintype "passive"))
      (node (ref "D29") (pin "2") (pinfunction "K_2") (pintype "passive"))
      (node (ref "D3") (pin "2") (pinfunction "K_2") (pintype "passive"))
      (node (ref "D30") (pin "2") (pinfunction "K_2") (pintype "passive"))
      (node (ref "D31") (pin "2") (pinfunction "K_2") (pintype "passive"))
      (node (ref "D32") (pin "2") (pinfunction "K_2") (pintype "passive"))
      (node (ref "D4") (pin "2") (pinfunction "K_2") (pintype "passive"))
      (node (ref "D5") (pin "2") (pinfunction "K_2") (pintype "passive"))
      (node (ref "D6") (pin "2") (pinfunction "K_2") (pintype "passive"))
      (node (ref "D7") (pin "2") (pinfunction "K_2") (pintype "passive"))
      (node (ref "D8") (pin "2") (pinfunction "K_2") (pintype "passive"))
      (node (ref "D9") (pin "2") (pinfunction "K_2") (pintype "passive"))
      (node (ref "J5") (pin "1") (pinfunction "1_1") (pintype "passive"))
      (node (ref "P9") (pin "5") (pinfunction "5_5") (pintype "passive"))
      (node (ref "R13") (pin "2") (pinfunction "TAP_2") (pintype "passive"))
      (node (ref "R13") (pin "3") (pinfunction "TOP_3") (pintype "passive"))
      (node (ref "R14") (pin "2") (pinfunction "TAP_2") (pintype "passive"))
      (node (ref "R14") (pin "3") (pinfunction "TOP_3") (pintype "passive"))
      (node (ref "R15") (pin "2") (pinfunction "TAP_2") (pintype "passive"))
      (node (ref "R15") (pin "3") (pinfunction "TOP_3") (pintype "passive"))
      (node (ref "R19") (pin "2") (pinfunction "2_2") (pintype "passive"))
      (node (ref "S1") (pin "1") (pinfunction "A1_1") (pintype "passive"))
      (node (ref "S1") (pin "2") (pinfunction "A2_2") (pintype "passive"))
      (node (ref "S1") (pin "3") (pinfunction "A3_3") (pintype "passive"))
      (node (ref "U1") (pin "20") (pinfunction "VCC_20") (pintype "power_in"))
      (node (ref "U2") (pin "20") (pinfunction "VCC_20") (pintype "power_in"))
      (node (ref "U3") (pin "1") (pinfunction "T/~{R}_1") (pintype "input"))
      (node (ref "U3") (pin "20") (pinfunction "VCC_20") (pintype "power_in"))
      (node (ref "U4") (pin "1") (pinfunction "T/~{R}_1") (pintype "input"))
      (node (ref "U4") (pin "20") (pinfunction "VCC_20") (pintype "power_in"))
      (node (ref "U5") (pin "1") (pinfunction "T/~{R}_1") (pintype "input"))
      (node (ref "U5") (pin "20") (pinfunction "VCC_20") (pintype "power_in"))
      (node (ref "U6") (pin "16") (pinfunction "VCC_16") (pintype "power_in"))
      (node (ref "U7") (pin "11") (pinfunction "~{CLR}_11") (pintype "input"))
      (node (ref "U7") (pin "16") (pinfunction "VCC_16") (pintype "power_in"))
      (node (ref "U7") (pin "2") (pinfunction "B_2") (pintype "input"))
      (node (ref "U7") (pin "3") (pinfunction "~{CLR}_3") (pintype "input"))
      (node (ref "U8") (pin "16") (pinfunction "VCC_16") (pintype "power_in"))
      (node (ref "U8") (pin "3") (pinfunction "~{CLR}_3") (pintype "input"))
      (node (ref "U9") (pin "14") (pinfunction "VDD_14") (pintype "power_in"))
    )
    (net (code "136") (name "unconnected-(P6-Pad1)") (class "Default")
      (node (ref "P6") (pin "1") (pinfunction "1_1") (pintype "passive"))
    )
    (net (code "137") (name "unconnected-(P6-Pad3)") (class "Default")
      (node (ref "P6") (pin "3") (pinfunction "3_3") (pintype "passive"))
    )
    (net (code "138") (name "unconnected-(P6-Pad5)") (class "Default")
      (node (ref "P6") (pin "5") (pinfunction "5_5") (pintype "passive"))
    )
    (net (code "139") (name "unconnected-(P6-Pad7)") (class "Default")
      (node (ref "P6") (pin "7") (pinfunction "7_7") (pintype "passive"))
    )
    (net (code "140") (name "unconnected-(P6-Pad9)") (class "Default")
      (node (ref "P6") (pin "9") (pinfunction "9_9") (pintype "passive"))
    )
    (net (code "141") (name "unconnected-(P6-Pad11)") (class "Default")
      (node (ref "P6") (pin "11") (pinfunction "11_11") (pintype "passive"))
    )
    (net (code "142") (name "unconnected-(P6-Pad13)") (class "Default")
      (node (ref "P6") (pin "13") (pinfunction "13_13") (pintype "passive"))
    )
    (net (code "143") (name "unconnected-(P6-Pad15)") (class "Default")
      (node (ref "P6") (pin "15") (pinfunction "15_15") (pintype "passive"))
    )
    (net (code "144") (name "unconnected-(P6-Pad17)") (class "Default")
      (node (ref "P6") (pin "17") (pinfunction "17_17") (pintype "passive"))
    )
    (net (code "145") (name "unconnected-(P6-Pad19)") (class "Default")
      (node (ref "P6") (pin "19") (pinfunction "19_19") (pintype "passive"))
    )
    (net (code "146") (name "unconnected-(P6-Pad21)") (class "Default")
      (node (ref "P6") (pin "21") (pinfunction "21_21") (pintype "passive"))
    )
    (net (code "147") (name "unconnected-(P6-Pad23)") (class "Default")
      (node (ref "P6") (pin "23") (pinfunction "23_23") (pintype "passive"))
    )
    (net (code "148") (name "unconnected-(P6-Pad25)") (class "Default")
      (node (ref "P6") (pin "25") (pinfunction "25_25") (pintype "passive"))
    )
    (net (code "149") (name "unconnected-(P6-Pad27)") (class "Default")
      (node (ref "P6") (pin "27") (pinfunction "27_27") (pintype "passive"))
    )
    (net (code "150") (name "unconnected-(P6-Pad29)") (class "Default")
      (node (ref "P6") (pin "29") (pinfunction "29_29") (pintype "passive"))
    )
    (net (code "151") (name "unconnected-(P6-Pad31)") (class "Default")
      (node (ref "P6") (pin "31") (pinfunction "31_31") (pintype "passive"))
    )
    (net (code "152") (name "unconnected-(P6-Pad33)") (class "Default")
      (node (ref "P6") (pin "33") (pinfunction "33_33") (pintype "passive"))
    )
    (net (code "153") (name "unconnected-(P6-Pad35)") (class "Default")
      (node (ref "P6") (pin "35") (pinfunction "35_35") (pintype "passive"))
    )
    (net (code "154") (name "unconnected-(P6-Pad37)") (class "Default")
      (node (ref "P6") (pin "37") (pinfunction "37_37") (pintype "passive"))
    )
    (net (code "155") (name "unconnected-(P6-Pad39)") (class "Default")
      (node (ref "P6") (pin "39") (pinfunction "39_39") (pintype "passive"))
    )
    (net (code "156") (name "unconnected-(P6-Pad41)") (class "Default")
      (node (ref "P6") (pin "41") (pinfunction "41_41") (pintype "passive"))
    )
    (net (code "157") (name "unconnected-(P6-Pad43)") (class "Default")
      (node (ref "P6") (pin "43") (pinfunction "43_43") (pintype "passive"))
    )
    (net (code "158") (name "unconnected-(P6-Pad45)") (class "Default")
      (node (ref "P6") (pin "45") (pinfunction "45_45") (pintype "passive"))
    )
    (net (code "159") (name "unconnected-(P6-Pad47)") (class "Default")
      (node (ref "P6") (pin "47") (pinfunction "47_47") (pintype "passive"))
    )
    (net (code "160") (name "unconnected-(P6-Pad49)") (class "Default")
      (node (ref "P6") (pin "49") (pinfunction "49_49") (pintype "passive"))
    )
    (net (code "161") (name "unconnected-(P8-Pad4)") (class "Default")
      (node (ref "P8") (pin "4") (pinfunction "4_4") (pintype "passive"))
    )
    (net (code "162") (name "unconnected-(P8-Pad5)") (class "Default")
      (node (ref "P8") (pin "5") (pinfunction "5_5") (pintype "passive"))
    )
    (net (code "163") (name "unconnected-(P8-Pad6)") (class "Default")
      (node (ref "P8") (pin "6") (pinfunction "6_6") (pintype "passive"))
    )
    (net (code "164") (name "unconnected-(P8-Pad7)") (class "Default")
      (node (ref "P8") (pin "7") (pinfunction "7_7") (pintype "passive"))
    )
    (net (code "165") (name "unconnected-(P8-Pad8)") (class "Default")
      (node (ref "P8") (pin "8") (pinfunction "8_8") (pintype "passive"))
    )
    (net (code "166") (name "unconnected-(P8-Pad9)") (class "Default")
      (node (ref "P8") (pin "9") (pinfunction "9_9") (pintype "passive"))
    )
    (net (code "167") (name "unconnected-(P8-Pad38)") (class "Default")
      (node (ref "P8") (pin "38") (pinfunction "38_38") (pintype "passive"))
    )
    (net (code "168") (name "unconnected-(P8-Pad40)") (class "Default")
      (node (ref "P8") (pin "40") (pinfunction "40_40") (pintype "passive"))
    )
    (net (code "169") (name "unconnected-(P9-Pad1)") (class "Default")
      (node (ref "P9") (pin "1") (pinfunction "1_1") (pintype "passive"))
    )
    (net (code "170") (name "unconnected-(P9-Pad2)") (class "Default")
      (node (ref "P9") (pin "2") (pinfunction "2_2") (pintype "passive"))
    )
    (net (code "171") (name "unconnected-(P9-Pad3)") (class "Default")
      (node (ref "P9") (pin "3") (pinfunction "3_3") (pintype "passive"))
    )
    (net (code "172") (name "unconnected-(P9-Pad4)") (class "Default")
      (node (ref "P9") (pin "4") (pinfunction "4_4") (pintype "passive"))
    )
    (net (code "173") (name "unconnected-(P9-Pad6)") (class "Default")
      (node (ref "P9") (pin "6") (pinfunction "6_6") (pintype "passive"))
    )
    (net (code "174") (name "unconnected-(P9-Pad7)") (class "Default")
      (node (ref "P9") (pin "7") (pinfunction "7_7") (pintype "passive"))
    )
    (net (code "175") (name "unconnected-(R7-Pad2)") (class "Default")
      (node (ref "R7") (pin "2") (pinfunction "2_2") (pintype "passive"))
    )
    (net (code "176") (name "unconnected-(U5-B0-Pad18)") (class "Default")
      (node (ref "U5") (pin "18") (pinfunction "B0_18") (pintype "bidirectional"))
    )
    (net (code "177") (name "unconnected-(U5-B1-Pad17)") (class "Default")
      (node (ref "U5") (pin "17") (pinfunction "B1_17") (pintype "bidirectional"))
    )
    (net (code "178") (name "unconnected-(U5-B2-Pad16)") (class "Default")
      (node (ref "U5") (pin "16") (pinfunction "B2_16") (pintype "bidirectional"))
    )
    (net (code "179") (name "unconnected-(U5-B3-Pad15)") (class "Default")
      (node (ref "U5") (pin "15") (pinfunction "B3_15") (pintype "bidirectional"))
    )
    (net (code "180") (name "unconnected-(U5-B4-Pad14)") (class "Default")
      (node (ref "U5") (pin "14") (pinfunction "B4_14") (pintype "bidirectional"))
    )
    (net (code "181") (name "unconnected-(U5-B5-Pad13)") (class "Default")
      (node (ref "U5") (pin "13") (pinfunction "B5_13") (pintype "bidirectional"))
    )
    (net (code "182") (name "unconnected-(U6-P<Qout-Pad7)") (class "Default")
      (node (ref "U6") (pin "7") (pinfunction "P<Qout_7") (pintype "output"))
    )
    (net (code "183") (name "unconnected-(U6-P>Qout-Pad5)") (class "Default")
      (node (ref "U6") (pin "5") (pinfunction "P>Qout_5") (pintype "output"))
    )
    (net (code "184") (name "unconnected-(U7A-~{Q}-Pad4)") (class "Default")
      (node (ref "U7") (pin "4") (pinfunction "~{Q}_4") (pintype "output"))
    )
    (net (code "185") (name "unconnected-(U7B-~{Q}-Pad12)") (class "Default")
      (node (ref "U7") (pin "12") (pinfunction "~{Q}_12") (pintype "output"))
    )
    (net (code "186") (name "unconnected-(U8A-Q-Pad13)") (class "Default")
      (node (ref "U8") (pin "13") (pinfunction "Q_13") (pintype "output"))
    )
    (net (code "187") (name "unconnected-(U8B-CX-Pad6)") (class "Default")
      (node (ref "U8") (pin "6") (pinfunction "CX_6") (pintype "passive"))
    )
    (net (code "188") (name "unconnected-(U8B-CX{slash}RX-Pad7)") (class "Default")
      (node (ref "U8") (pin "7") (pinfunction "CX/RX_7") (pintype "passive"))
    )
    (net (code "189") (name "unconnected-(U8B-Q-Pad5)") (class "Default")
      (node (ref "U8") (pin "5") (pinfunction "Q_5") (pintype "output"))
    )
    (net (code "190") (name "unconnected-(U8B-~{Q}-Pad12)") (class "Default")
      (node (ref "U8") (pin "12") (pinfunction "~{Q}_12") (pintype "output"))
    )
  )
)
